# UMN_HASP_2015_Front_End_Board1.net
KiCad netlist of a schematic drawn in EAGLE
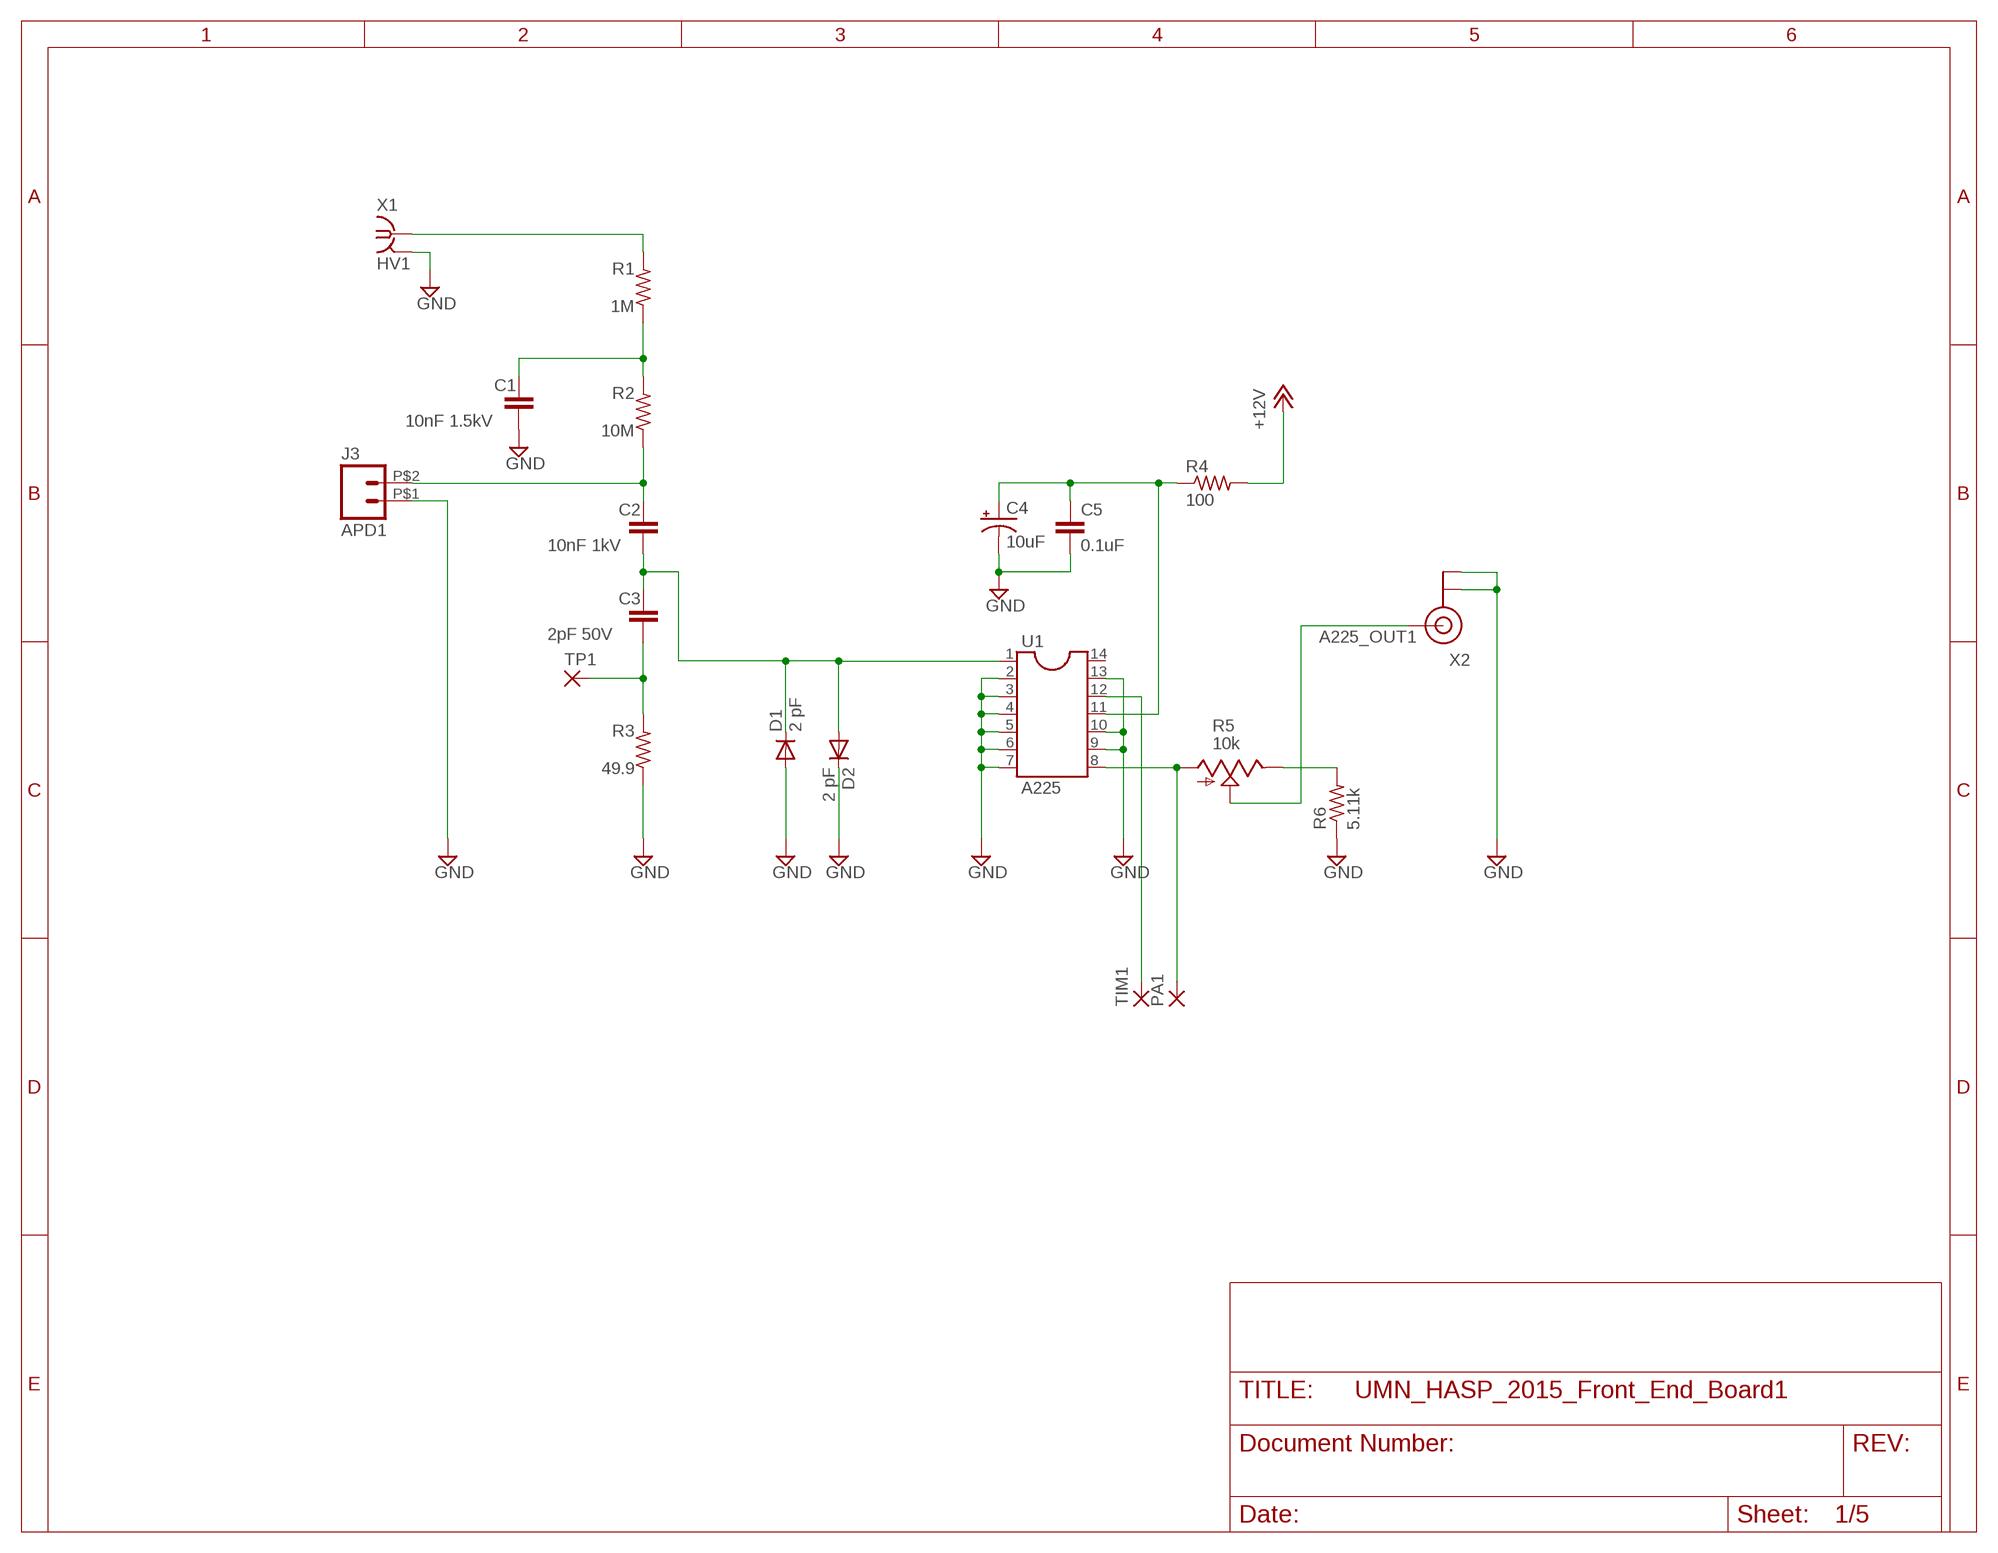
[diagram p0: schematic, sheet 1]
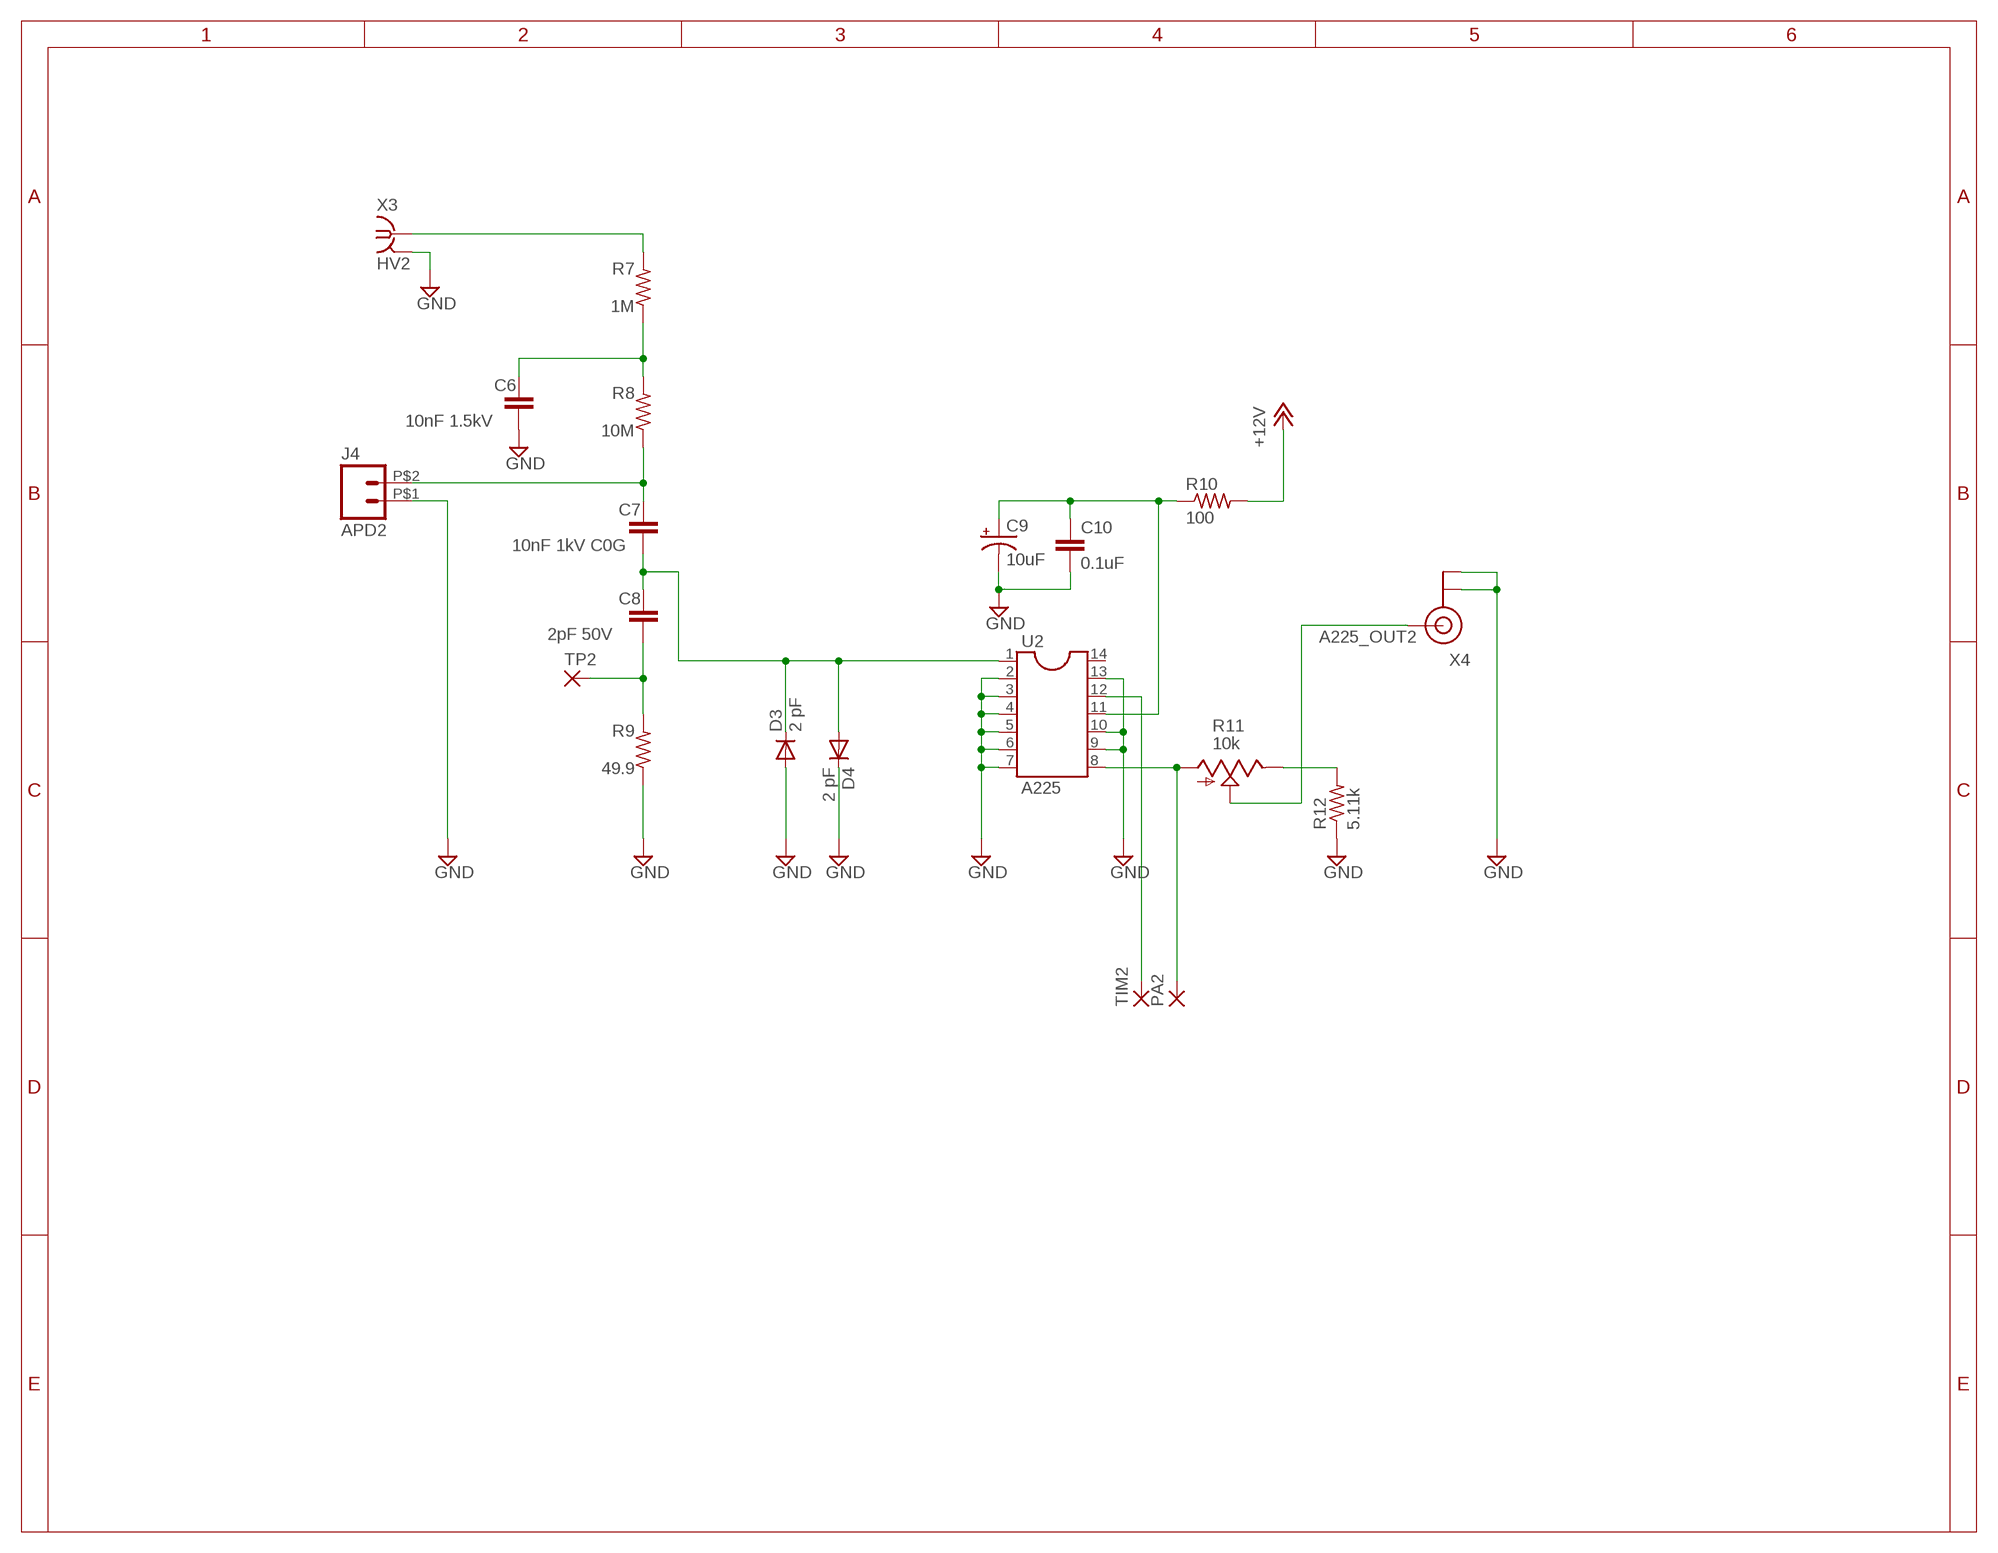
[diagram p1: schematic, sheet 2]
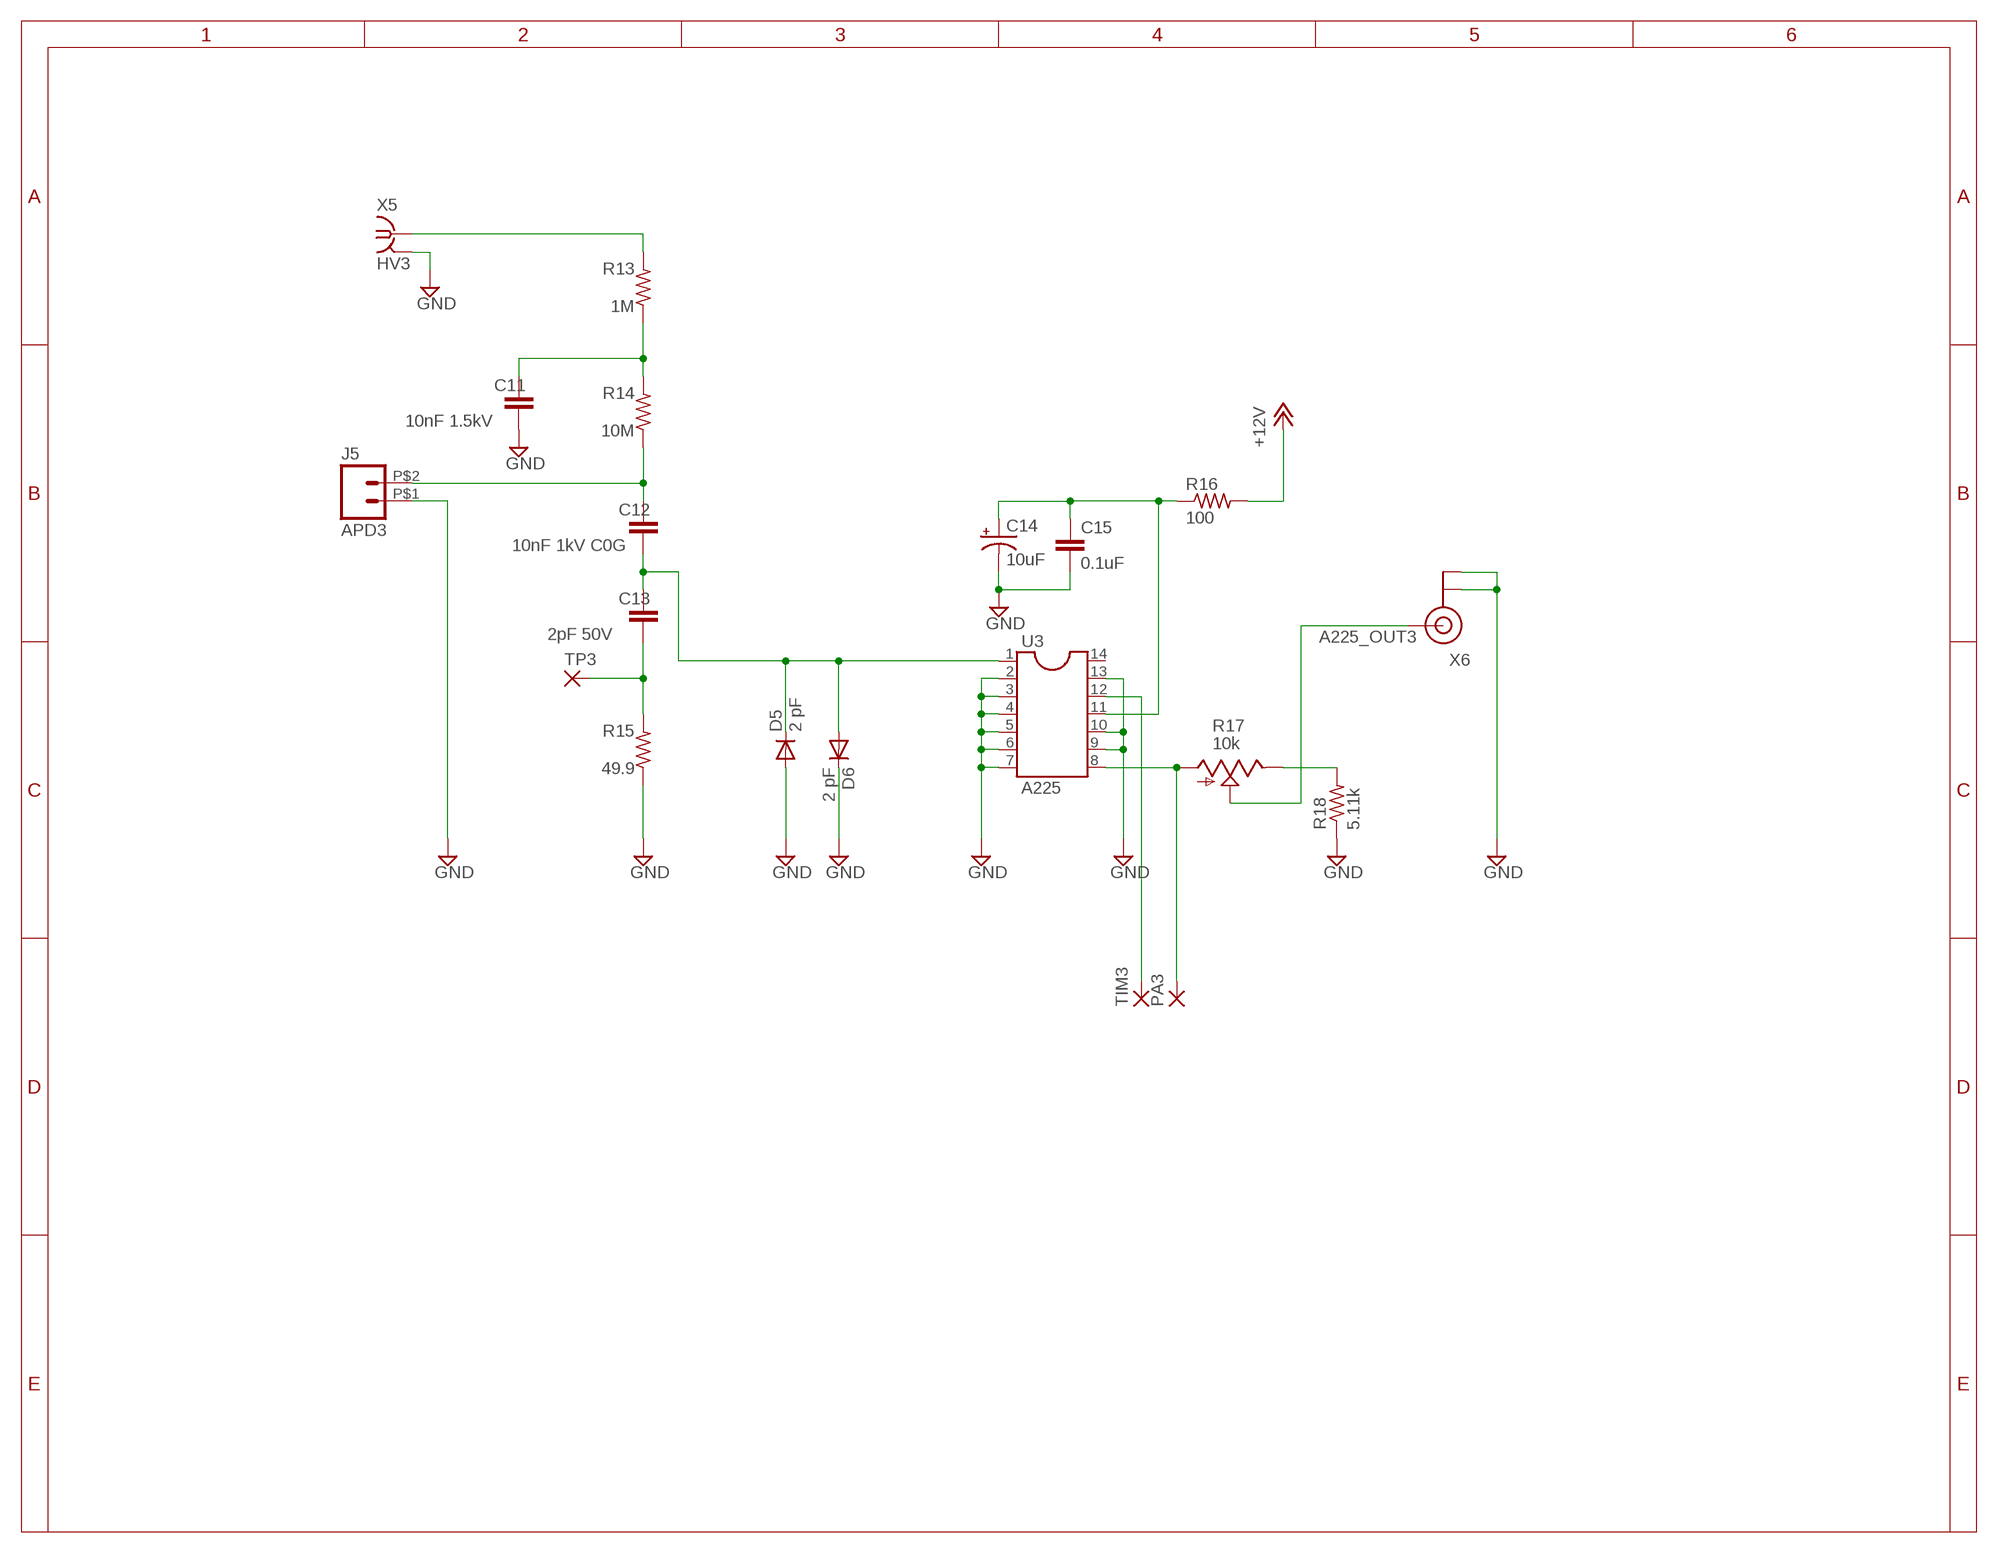
[diagram p2: schematic, sheet 3]
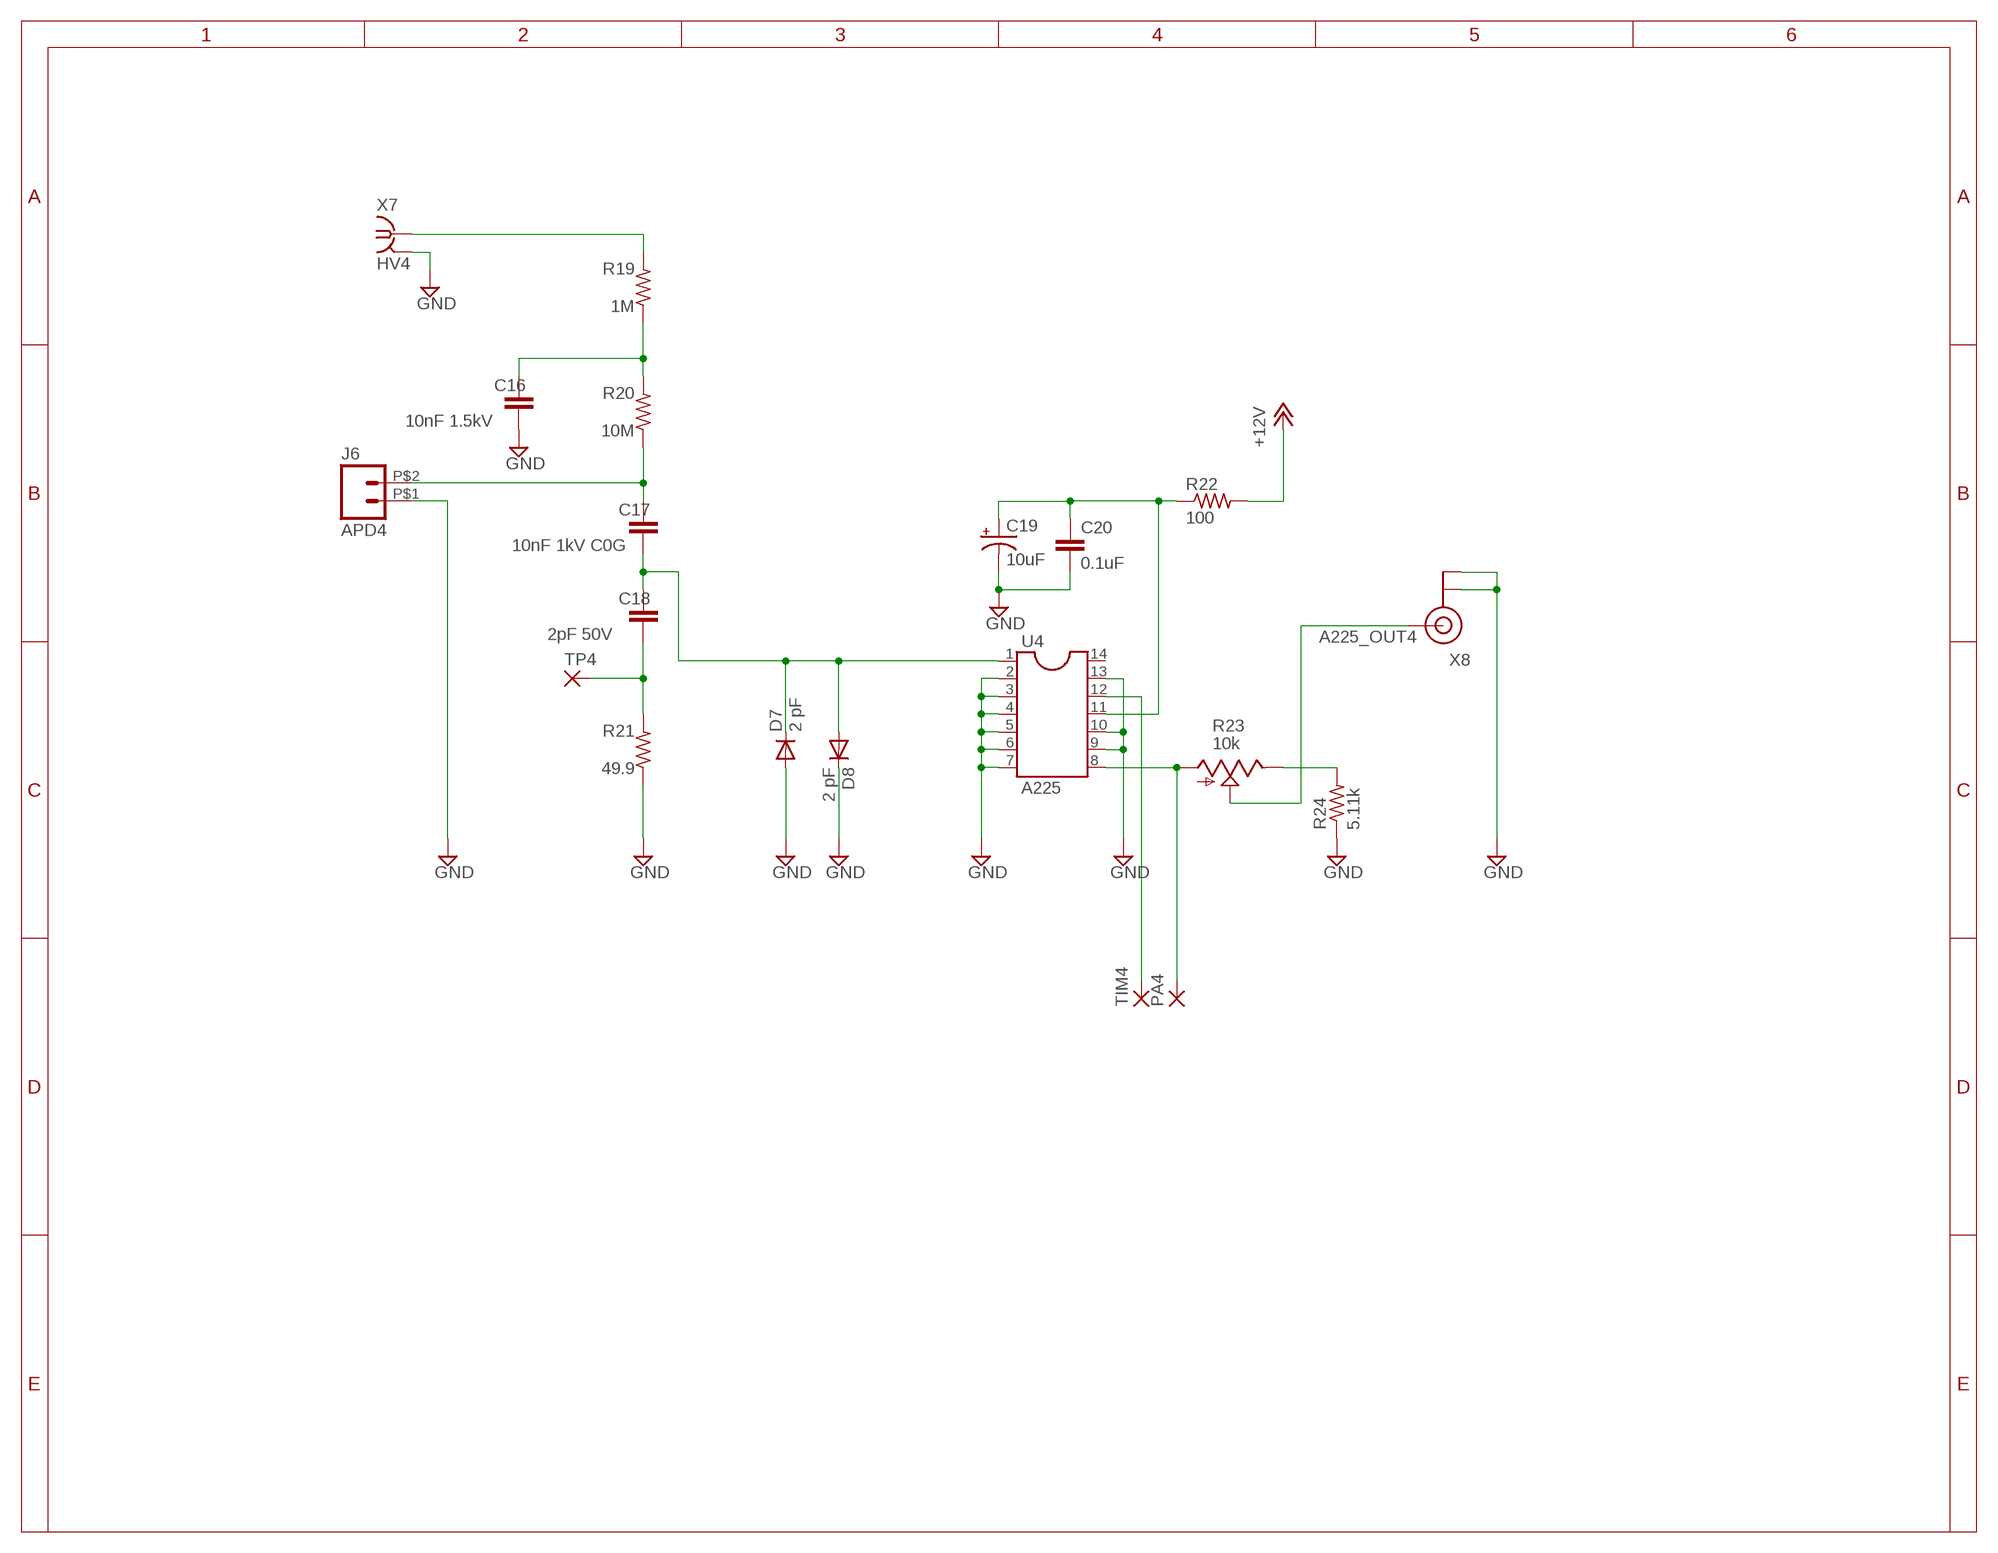
[diagram p3: schematic, sheet 4]
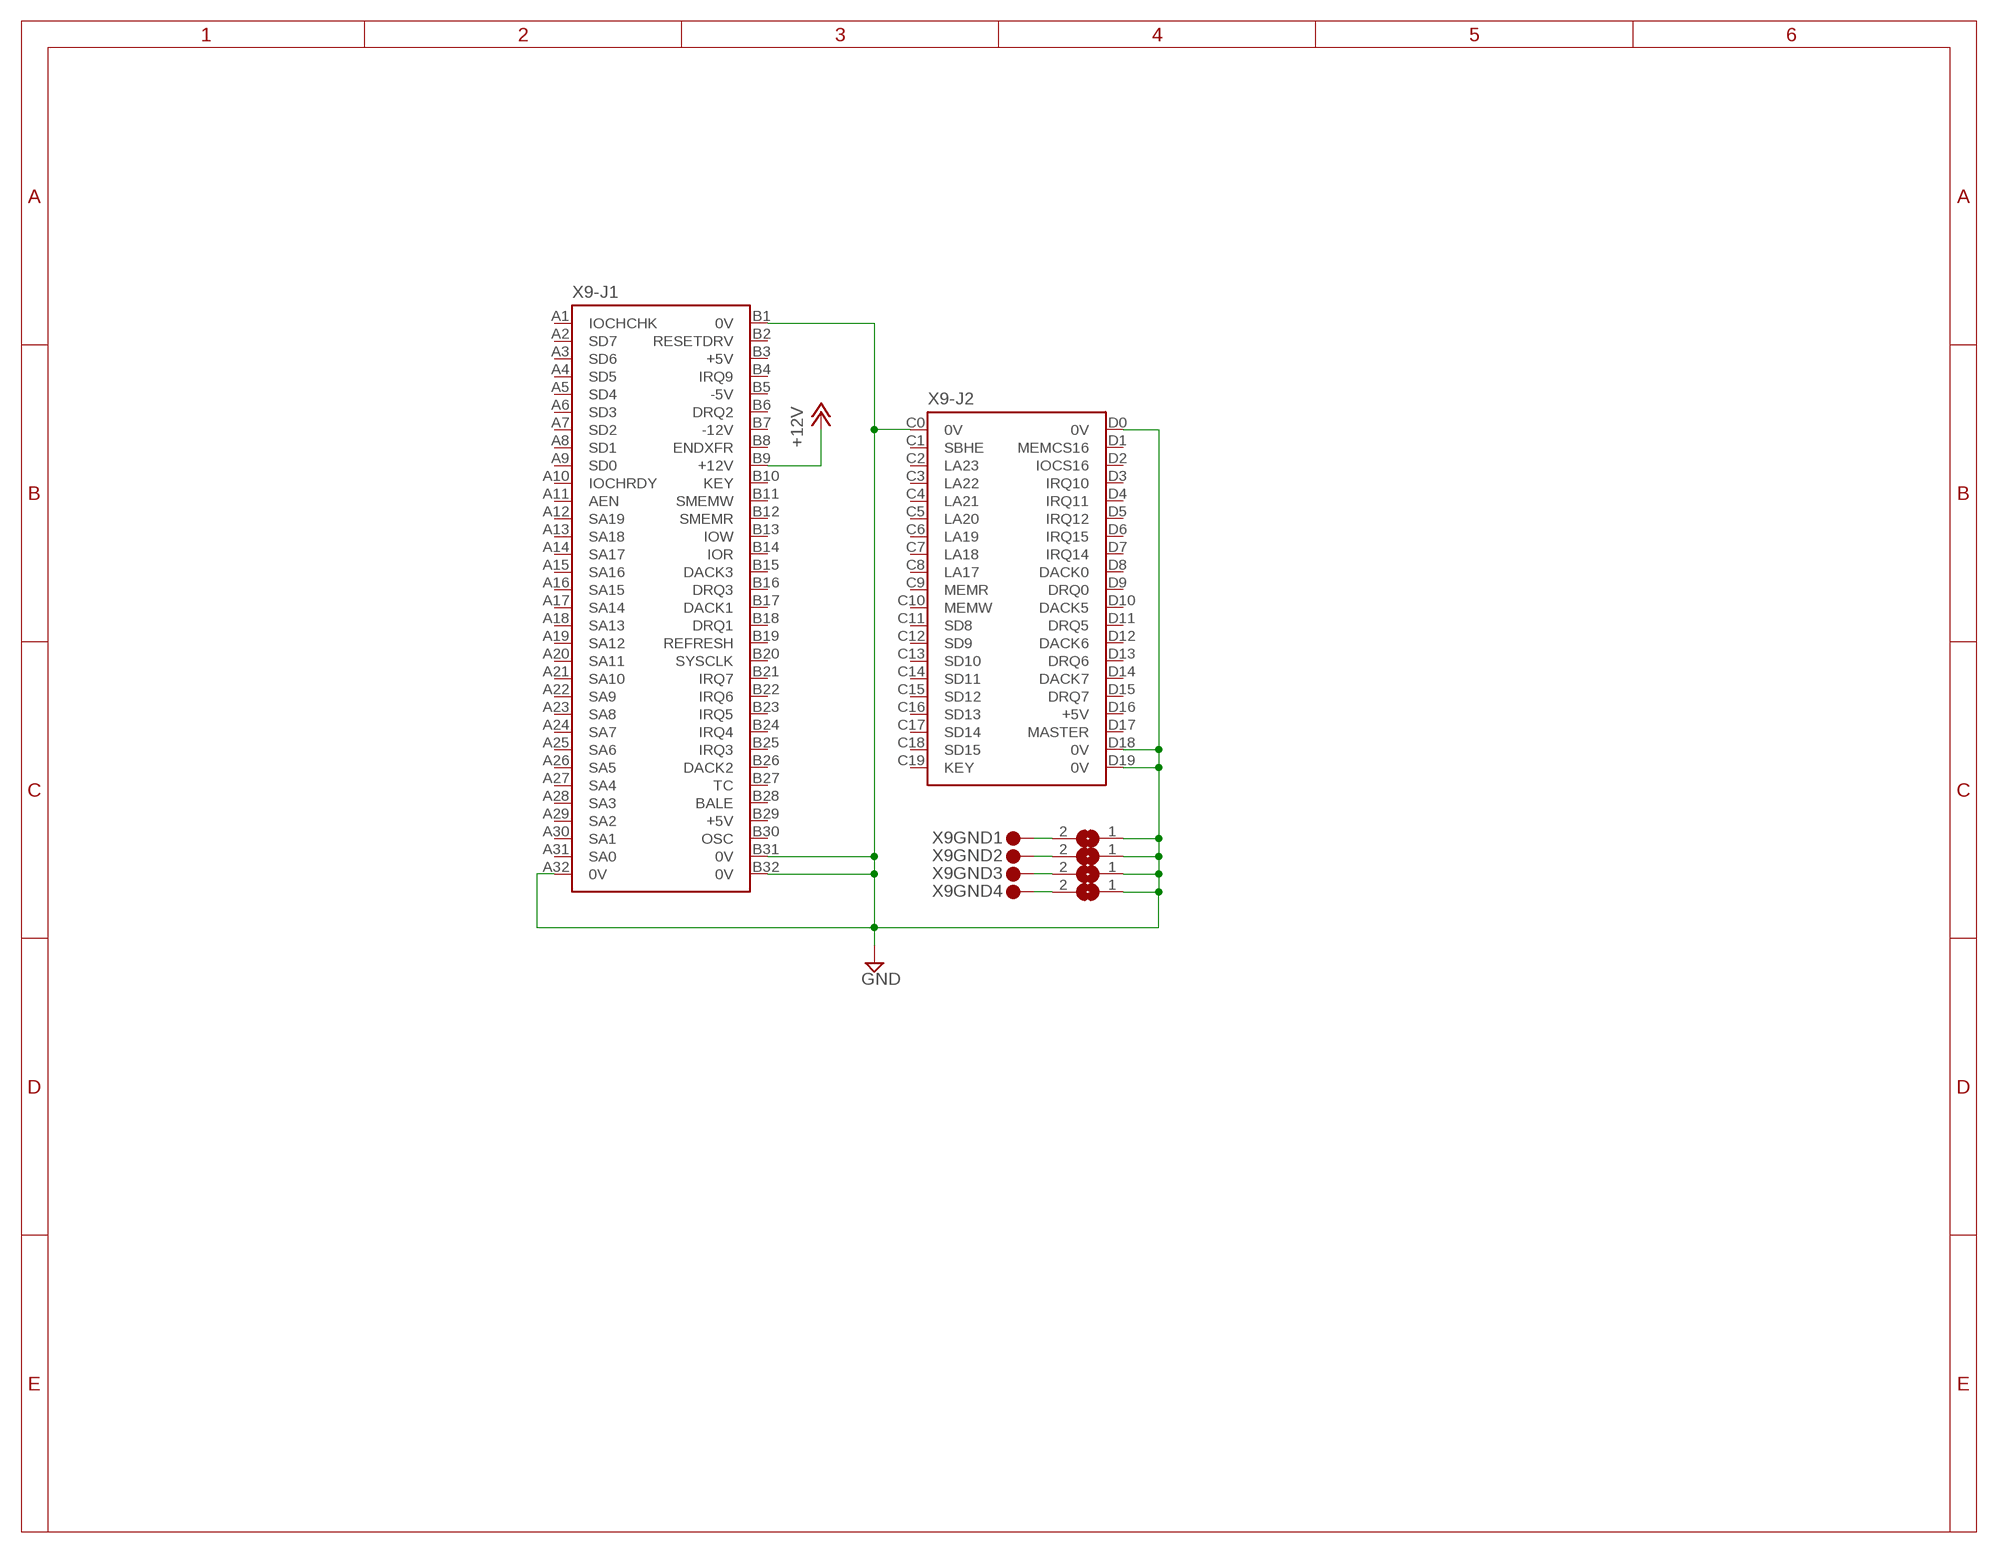
[diagram p4: schematic, sheet 5]

(export (version "E")
  (design (tool "Eeschema 10.0.6"))
  (components
    (comp (ref "SJ1") (value "SJ") (footprint "eagle-import:SJ") (libsource (lib "eagle-import") (part "SJ")))
    (comp (ref "SJ2") (value "SJ") (footprint "eagle-import:SJ") (libsource (lib "eagle-import") (part "SJ")))
    (comp (ref "SJ3") (value "SJ") (footprint "eagle-import:SJ") (libsource (lib "eagle-import") (part "SJ")))
    (comp (ref "SJ4") (value "SJ") (footprint "eagle-import:SJ") (libsource (lib "eagle-import") (part "SJ")))
    (comp (ref "X9")
      (value "PC104_STANDARD1")
      (footprint "eagle-import:PC104-STANDARD")
      (libsource (lib "eagle-import") (part "PC104_STANDARD1"))
    )
    (comp (ref "C6")
      (value "10nF 1.5kV")
      (footprint "eagle-import:C1206K")
      (libsource (lib "eagle-import") (part "C-EUC1206K"))
    )
    (comp (ref "C7")
      (value "10nF 1kV C0G")
      (footprint "eagle-import:C050-050X075")
      (libsource (lib "eagle-import") (part "C-EU050-050X075"))
    )
    (comp (ref "C8")
      (value "2pF 50V")
      (footprint "eagle-import:C0402")
      (libsource (lib "eagle-import") (part "C-EUC0402"))
    )
    (comp (ref "C9")
      (value "10uF")
      (footprint "eagle-import:C_6032-28R")
      (libsource (lib "eagle-import") (part "CPOL-USC/6032-28R"))
    )
    (comp (ref "C10")
      (value "0.1uF")
      (footprint "eagle-import:C0603K")
      (libsource (lib "eagle-import") (part "C-EUC0603K"))
    )
    (comp (ref "D3")
      (value "2 pF")
      (footprint "eagle-import:SOD323-R")
      (libsource (lib "eagle-import") (part "DIODE-SOD323-R"))
    )
    (comp (ref "D4")
      (value "2 pF")
      (footprint "eagle-import:SOD323-R")
      (libsource (lib "eagle-import") (part "DIODE-SOD323-R"))
    )
    (comp (ref "J4")
      (value "M02PTH2")
      (footprint "eagle-import:1X02_BIG")
      (libsource (lib "eagle-import") (part "M02PTH2"))
    )
    (comp (ref "PA2")
      (value "WIREPADSMD1,27-254")
      (footprint "eagle-import:SMD1,27-2,54")
      (libsource (lib "eagle-import") (part "WIREPADSMD1,27-254"))
    )
    (comp (ref "R7")
      (value "1M")
      (footprint "eagle-import:R1206")
      (libsource (lib "eagle-import") (part "R-US_R1206"))
    )
    (comp (ref "R8")
      (value "10M")
      (footprint "eagle-import:R1206")
      (libsource (lib "eagle-import") (part "R-US_R1206"))
    )
    (comp (ref "R9")
      (value "49.9")
      (footprint "eagle-import:R0603")
      (libsource (lib "eagle-import") (part "R-US_R0603"))
    )
    (comp (ref "R10")
      (value "100")
      (footprint "eagle-import:R0603")
      (libsource (lib "eagle-import") (part "R-US_R0603"))
    )
    (comp (ref "R11")
      (value "10k")
      (footprint "eagle-import:3223J")
      (libsource (lib "eagle-import") (part "TRIM_US-3223J"))
    )
    (comp (ref "R12")
      (value "5.11k")
      (footprint "eagle-import:R0603")
      (libsource (lib "eagle-import") (part "R-US_R0603"))
    )
    (comp (ref "TIM2")
      (value "WIREPADSMD1,27-254")
      (footprint "eagle-import:SMD1,27-2,54")
      (libsource (lib "eagle-import") (part "WIREPADSMD1,27-254"))
    )
    (comp (ref "TP2")
      (value "WIREPADSMD1,27-254")
      (footprint "eagle-import:SMD1,27-2,54")
      (libsource (lib "eagle-import") (part "WIREPADSMD1,27-254"))
    )
    (comp (ref "U2")
      (value "A225")
      (footprint "eagle-import:SOCKET-14")
      (libsource (lib "eagle-import") (part "DIL14S"))
    )
    (comp (ref "X3")
      (value "HV2")
      (footprint "eagle-import:BU-SMA-V")
      (libsource (lib "eagle-import") (part "BU-SMA-V"))
    )
    (comp (ref "X4")
      (value "U.FL")
      (footprint "eagle-import:U.FL")
      (libsource (lib "eagle-import") (part "U.FL"))
    )
    (comp (ref "C16")
      (value "10nF 1.5kV")
      (footprint "eagle-import:C1206K")
      (libsource (lib "eagle-import") (part "C-EUC1206K"))
    )
    (comp (ref "C17")
      (value "10nF 1kV C0G")
      (footprint "eagle-import:C050-050X075")
      (libsource (lib "eagle-import") (part "C-EU050-050X075"))
    )
    (comp (ref "C18")
      (value "2pF 50V")
      (footprint "eagle-import:C0402")
      (libsource (lib "eagle-import") (part "C-EUC0402"))
    )
    (comp (ref "C19")
      (value "10uF")
      (footprint "eagle-import:C_6032-28R")
      (libsource (lib "eagle-import") (part "CPOL-USC/6032-28R"))
    )
    (comp (ref "C20")
      (value "0.1uF")
      (footprint "eagle-import:C0603K")
      (libsource (lib "eagle-import") (part "C-EUC0603K"))
    )
    (comp (ref "D7")
      (value "2 pF")
      (footprint "eagle-import:SOD323-R")
      (libsource (lib "eagle-import") (part "DIODE-SOD323-R"))
    )
    (comp (ref "D8")
      (value "2 pF")
      (footprint "eagle-import:SOD323-R")
      (libsource (lib "eagle-import") (part "DIODE-SOD323-R"))
    )
    (comp (ref "J6")
      (value "M02PTH2")
      (footprint "eagle-import:1X02_BIG")
      (libsource (lib "eagle-import") (part "M02PTH2"))
    )
    (comp (ref "PA4")
      (value "WIREPADSMD1,27-254")
      (footprint "eagle-import:SMD1,27-2,54")
      (libsource (lib "eagle-import") (part "WIREPADSMD1,27-254"))
    )
    (comp (ref "R19")
      (value "1M")
      (footprint "eagle-import:R1206")
      (libsource (lib "eagle-import") (part "R-US_R1206"))
    )
    (comp (ref "R20")
      (value "10M")
      (footprint "eagle-import:R1206")
      (libsource (lib "eagle-import") (part "R-US_R1206"))
    )
    (comp (ref "R21")
      (value "49.9")
      (footprint "eagle-import:R0603")
      (libsource (lib "eagle-import") (part "R-US_R0603"))
    )
    (comp (ref "R22")
      (value "100")
      (footprint "eagle-import:R0603")
      (libsource (lib "eagle-import") (part "R-US_R0603"))
    )
    (comp (ref "R23")
      (value "10k")
      (footprint "eagle-import:3223J")
      (libsource (lib "eagle-import") (part "TRIM_US-3223J"))
    )
    (comp (ref "R24")
      (value "5.11k")
      (footprint "eagle-import:R0603")
      (libsource (lib "eagle-import") (part "R-US_R0603"))
    )
    (comp (ref "TIM4")
      (value "WIREPADSMD1,27-254")
      (footprint "eagle-import:SMD1,27-2,54")
      (libsource (lib "eagle-import") (part "WIREPADSMD1,27-254"))
    )
    (comp (ref "TP4")
      (value "WIREPADSMD1,27-254")
      (footprint "eagle-import:SMD1,27-2,54")
      (libsource (lib "eagle-import") (part "WIREPADSMD1,27-254"))
    )
    (comp (ref "U4")
      (value "A225")
      (footprint "eagle-import:SOCKET-14")
      (libsource (lib "eagle-import") (part "DIL14S"))
    )
    (comp (ref "X7")
      (value "HV4")
      (footprint "eagle-import:BU-SMA-V")
      (libsource (lib "eagle-import") (part "BU-SMA-V"))
    )
    (comp (ref "X8")
      (value "U.FL")
      (footprint "eagle-import:U.FL")
      (libsource (lib "eagle-import") (part "U.FL"))
    )
    (comp (ref "C1")
      (value "10nF 1.5kV")
      (footprint "eagle-import:C1206K")
      (libsource (lib "eagle-import") (part "C-EUC1206K"))
    )
    (comp (ref "C2")
      (value "10nF 1kV")
      (footprint "eagle-import:C050-050X075")
      (libsource (lib "eagle-import") (part "C-EU050-050X075"))
    )
    (comp (ref "C3")
      (value "2pF 50V")
      (footprint "eagle-import:C0402")
      (libsource (lib "eagle-import") (part "C-EUC0402"))
    )
    (comp (ref "C4")
      (value "10uF")
      (footprint "eagle-import:C_6032-28R")
      (libsource (lib "eagle-import") (part "CPOL-USC/6032-28R"))
    )
    (comp (ref "C5")
      (value "0.1uF")
      (footprint "eagle-import:C0603K")
      (libsource (lib "eagle-import") (part "C-EUC0603K"))
    )
    (comp (ref "D1")
      (value "2 pF")
      (footprint "eagle-import:SOD323-R")
      (libsource (lib "eagle-import") (part "DIODE-SOD323-R"))
    )
    (comp (ref "D2")
      (value "2 pF")
      (footprint "eagle-import:SOD323-R")
      (libsource (lib "eagle-import") (part "DIODE-SOD323-R"))
    )
    (comp (ref "J3")
      (value "M02PTH2")
      (footprint "eagle-import:1X02_BIG")
      (libsource (lib "eagle-import") (part "M02PTH2"))
    )
    (comp (ref "PA1")
      (value "WIREPADSMD1,27-254")
      (footprint "eagle-import:SMD1,27-2,54")
      (libsource (lib "eagle-import") (part "WIREPADSMD1,27-254"))
    )
    (comp (ref "R1")
      (value "1M")
      (footprint "eagle-import:R1206")
      (libsource (lib "eagle-import") (part "R-US_R1206"))
    )
    (comp (ref "R2")
      (value "10M")
      (footprint "eagle-import:R1206")
      (libsource (lib "eagle-import") (part "R-US_R1206"))
    )
    (comp (ref "R3")
      (value "49.9")
      (footprint "eagle-import:R0603")
      (libsource (lib "eagle-import") (part "R-US_R0603"))
    )
    (comp (ref "R4")
      (value "100")
      (footprint "eagle-import:R0603")
      (libsource (lib "eagle-import") (part "R-US_R0603"))
    )
    (comp (ref "R5")
      (value "10k")
      (footprint "eagle-import:3223J")
      (libsource (lib "eagle-import") (part "TRIM_US-3223J"))
    )
    (comp (ref "R6")
      (value "5.11k")
      (footprint "eagle-import:R0603")
      (libsource (lib "eagle-import") (part "R-US_R0603"))
    )
    (comp (ref "TIM1")
      (value "WIREPADSMD1,27-254")
      (footprint "eagle-import:SMD1,27-2,54")
      (libsource (lib "eagle-import") (part "WIREPADSMD1,27-254"))
    )
    (comp (ref "TP1")
      (value "WIREPADSMD1,27-254")
      (footprint "eagle-import:SMD1,27-2,54")
      (libsource (lib "eagle-import") (part "WIREPADSMD1,27-254"))
    )
    (comp (ref "U1")
      (value "A225")
      (footprint "eagle-import:SOCKET-14")
      (libsource (lib "eagle-import") (part "DIL14S"))
    )
    (comp (ref "X1")
      (value "HV1")
      (footprint "eagle-import:BU-SMA-V")
      (libsource (lib "eagle-import") (part "BU-SMA-V"))
    )
    (comp (ref "X2")
      (value "U.FL")
      (footprint "eagle-import:U.FL")
      (libsource (lib "eagle-import") (part "U.FL"))
    )
    (comp (ref "C11")
      (value "10nF 1.5kV")
      (footprint "eagle-import:C1206K")
      (libsource (lib "eagle-import") (part "C-EUC1206K"))
    )
    (comp (ref "C12")
      (value "10nF 1kV C0G")
      (footprint "eagle-import:C050-050X075")
      (libsource (lib "eagle-import") (part "C-EU050-050X075"))
    )
    (comp (ref "C13")
      (value "2pF 50V")
      (footprint "eagle-import:C0402")
      (libsource (lib "eagle-import") (part "C-EUC0402"))
    )
    (comp (ref "C14")
      (value "10uF")
      (footprint "eagle-import:C_6032-28R")
      (libsource (lib "eagle-import") (part "CPOL-USC/6032-28R"))
    )
    (comp (ref "C15")
      (value "0.1uF")
      (footprint "eagle-import:C0603K")
      (libsource (lib "eagle-import") (part "C-EUC0603K"))
    )
    (comp (ref "D5")
      (value "2 pF")
      (footprint "eagle-import:SOD323-R")
      (libsource (lib "eagle-import") (part "DIODE-SOD323-R"))
    )
    (comp (ref "D6")
      (value "2 pF")
      (footprint "eagle-import:SOD323-R")
      (libsource (lib "eagle-import") (part "DIODE-SOD323-R"))
    )
    (comp (ref "J5")
      (value "M02PTH2")
      (footprint "eagle-import:1X02_BIG")
      (libsource (lib "eagle-import") (part "M02PTH2"))
    )
    (comp (ref "PA3")
      (value "WIREPADSMD1,27-254")
      (footprint "eagle-import:SMD1,27-2,54")
      (libsource (lib "eagle-import") (part "WIREPADSMD1,27-254"))
    )
    (comp (ref "R13")
      (value "1M")
      (footprint "eagle-import:R1206")
      (libsource (lib "eagle-import") (part "R-US_R1206"))
    )
    (comp (ref "R14")
      (value "10M")
      (footprint "eagle-import:R1206")
      (libsource (lib "eagle-import") (part "R-US_R1206"))
    )
    (comp (ref "R15")
      (value "49.9")
      (footprint "eagle-import:R0603")
      (libsource (lib "eagle-import") (part "R-US_R0603"))
    )
    (comp (ref "R16")
      (value "100")
      (footprint "eagle-import:R0603")
      (libsource (lib "eagle-import") (part "R-US_R0603"))
    )
    (comp (ref "R17")
      (value "10k")
      (footprint "eagle-import:3223J")
      (libsource (lib "eagle-import") (part "TRIM_US-3223J"))
    )
    (comp (ref "R18")
      (value "5.11k")
      (footprint "eagle-import:R0603")
      (libsource (lib "eagle-import") (part "R-US_R0603"))
    )
    (comp (ref "TIM3")
      (value "WIREPADSMD1,27-254")
      (footprint "eagle-import:SMD1,27-2,54")
      (libsource (lib "eagle-import") (part "WIREPADSMD1,27-254"))
    )
    (comp (ref "TP3")
      (value "WIREPADSMD1,27-254")
      (footprint "eagle-import:SMD1,27-2,54")
      (libsource (lib "eagle-import") (part "WIREPADSMD1,27-254"))
    )
    (comp (ref "U3")
      (value "A225")
      (footprint "eagle-import:SOCKET-14")
      (libsource (lib "eagle-import") (part "DIL14S"))
    )
    (comp (ref "X5")
      (value "HV3")
      (footprint "eagle-import:BU-SMA-V")
      (libsource (lib "eagle-import") (part "BU-SMA-V"))
    )
    (comp (ref "X6")
      (value "U.FL")
      (footprint "eagle-import:U.FL")
      (libsource (lib "eagle-import") (part "U.FL"))
    )
  )
  (nets
    (net (code "1") (name "+12V") (class "Default")
      (node (ref "R10") (pin "2") (pinfunction "2_2") (pintype "passive"))
      (node (ref "R16") (pin "2") (pinfunction "2_2") (pintype "passive"))
      (node (ref "R22") (pin "2") (pinfunction "2_2") (pintype "passive"))
      (node (ref "R4") (pin "2") (pinfunction "2_2") (pintype "passive"))
      (node (ref "X9") (pin "B9") (pinfunction "+12V_B9") (pintype "passive"))
    )
    (net (code "2") (name "A225_OUT1") (class "Default")
      (node (ref "R5") (pin "2") (pinfunction "S_2") (pintype "passive"))
      (node (ref "X2") (pin "P$3") (pinfunction "SIGNAL_P$3") (pintype "bidirectional"))
    )
    (net (code "3") (name "A225_OUT2") (class "Default")
      (node (ref "R11") (pin "2") (pinfunction "S_2") (pintype "passive"))
      (node (ref "X4") (pin "P$3") (pinfunction "SIGNAL_P$3") (pintype "bidirectional"))
    )
    (net (code "4") (name "A225_OUT3") (class "Default")
      (node (ref "R17") (pin "2") (pinfunction "S_2") (pintype "passive"))
      (node (ref "X6") (pin "P$3") (pinfunction "SIGNAL_P$3") (pintype "bidirectional"))
    )
    (net (code "5") (name "A225_OUT4") (class "Default")
      (node (ref "R23") (pin "2") (pinfunction "S_2") (pintype "passive"))
      (node (ref "X8") (pin "P$3") (pinfunction "SIGNAL_P$3") (pintype "bidirectional"))
    )
    (net (code "6") (name "APD1") (class "Default")
      (node (ref "C2") (pin "1") (pinfunction "1_1") (pintype "passive"))
      (node (ref "J3") (pin "P$2") (pinfunction "2_P$2") (pintype "passive"))
      (node (ref "R2") (pin "1") (pinfunction "1_1") (pintype "passive"))
    )
    (net (code "7") (name "APD2") (class "Default")
      (node (ref "C7") (pin "1") (pinfunction "1_1") (pintype "passive"))
      (node (ref "J4") (pin "P$2") (pinfunction "2_P$2") (pintype "passive"))
      (node (ref "R8") (pin "1") (pinfunction "1_1") (pintype "passive"))
    )
    (net (code "8") (name "APD3") (class "Default")
      (node (ref "C12") (pin "1") (pinfunction "1_1") (pintype "passive"))
      (node (ref "J5") (pin "P$2") (pinfunction "2_P$2") (pintype "passive"))
      (node (ref "R14") (pin "1") (pinfunction "1_1") (pintype "passive"))
    )
    (net (code "9") (name "APD4") (class "Default")
      (node (ref "C17") (pin "1") (pinfunction "1_1") (pintype "passive"))
      (node (ref "J6") (pin "P$2") (pinfunction "2_P$2") (pintype "passive"))
      (node (ref "R20") (pin "1") (pinfunction "1_1") (pintype "passive"))
    )
    (net (code "10") (name "GND") (class "Default")
      (node (ref "C1") (pin "2") (pinfunction "2_2") (pintype "passive"))
      (node (ref "C10") (pin "2") (pinfunction "2_2") (pintype "passive"))
      (node (ref "C11") (pin "2") (pinfunction "2_2") (pintype "passive"))
      (node (ref "C14") (pin "-") (pinfunction "-_-") (pintype "passive"))
      (node (ref "C15") (pin "2") (pinfunction "2_2") (pintype "passive"))
      (node (ref "C16") (pin "2") (pinfunction "2_2") (pintype "passive"))
      (node (ref "C19") (pin "-") (pinfunction "-_-") (pintype "passive"))
      (node (ref "C20") (pin "2") (pinfunction "2_2") (pintype "passive"))
      (node (ref "C4") (pin "-") (pinfunction "-_-") (pintype "passive"))
      (node (ref "C5") (pin "2") (pinfunction "2_2") (pintype "passive"))
      (node (ref "C6") (pin "2") (pinfunction "2_2") (pintype "passive"))
      (node (ref "C9") (pin "-") (pinfunction "-_-") (pintype "passive"))
      (node (ref "D1") (pin "A") (pinfunction "A_A") (pintype "passive"))
      (node (ref "D2") (pin "C") (pinfunction "C_C") (pintype "passive"))
      (node (ref "D3") (pin "A") (pinfunction "A_A") (pintype "passive"))
      (node (ref "D4") (pin "C") (pinfunction "C_C") (pintype "passive"))
      (node (ref "D5") (pin "A") (pinfunction "A_A") (pintype "passive"))
      (node (ref "D6") (pin "C") (pinfunction "C_C") (pintype "passive"))
      (node (ref "D7") (pin "A") (pinfunction "A_A") (pintype "passive"))
      (node (ref "D8") (pin "C") (pinfunction "C_C") (pintype "passive"))
      (node (ref "J3") (pin "P$1") (pinfunction "1_P$1") (pintype "passive"))
      (node (ref "J4") (pin "P$1") (pinfunction "1_P$1") (pintype "passive"))
      (node (ref "J5") (pin "P$1") (pinfunction "1_P$1") (pintype "passive"))
      (node (ref "J6") (pin "P$1") (pinfunction "1_P$1") (pintype "passive"))
      (node (ref "R12") (pin "1") (pinfunction "1_1") (pintype "passive"))
      (node (ref "R15") (pin "1") (pinfunction "1_1") (pintype "passive"))
      (node (ref "R18") (pin "1") (pinfunction "1_1") (pintype "passive"))
      (node (ref "R21") (pin "1") (pinfunction "1_1") (pintype "passive"))
      (node (ref "R24") (pin "1") (pinfunction "1_1") (pintype "passive"))
      (node (ref "R3") (pin "1") (pinfunction "1_1") (pintype "passive"))
      (node (ref "R6") (pin "1") (pinfunction "1_1") (pintype "passive"))
      (node (ref "R9") (pin "1") (pinfunction "1_1") (pintype "passive"))
      (node (ref "SJ1") (pin "1") (pinfunction "1_1") (pintype "passive"))
      (node (ref "SJ2") (pin "1") (pinfunction "1_1") (pintype "passive"))
      (node (ref "SJ3") (pin "1") (pinfunction "1_1") (pintype "passive"))
      (node (ref "SJ4") (pin "1") (pinfunction "1_1") (pintype "passive"))
      (node (ref "U1") (pin "10") (pinfunction "10_10") (pintype "passive"))
      (node (ref "U1") (pin "13") (pinfunction "13_13") (pintype "passive"))
      (node (ref "U1") (pin "2") (pinfunction "2_2") (pintype "passive"))
      (node (ref "U1") (pin "3") (pinfunction "3_3") (pintype "passive"))
      (node (ref "U1") (pin "4") (pinfunction "4_4") (pintype "passive"))
      (node (ref "U1") (pin "5") (pinfunction "5_5") (pintype "passive"))
      (node (ref "U1") (pin "6") (pinfunction "6_6") (pintype "passive"))
      (node (ref "U1") (pin "7") (pinfunction "7_7") (pintype "passive"))
      (node (ref "U1") (pin "9") (pinfunction "9_9") (pintype "passive"))
      (node (ref "U2") (pin "10") (pinfunction "10_10") (pintype "passive"))
      (node (ref "U2") (pin "13") (pinfunction "13_13") (pintype "passive"))
      (node (ref "U2") (pin "2") (pinfunction "2_2") (pintype "passive"))
      (node (ref "U2") (pin "3") (pinfunction "3_3") (pintype "passive"))
      (node (ref "U2") (pin "4") (pinfunction "4_4") (pintype "passive"))
      (node (ref "U2") (pin "5") (pinfunction "5_5") (pintype "passive"))
      (node (ref "U2") (pin "6") (pinfunction "6_6") (pintype "passive"))
      (node (ref "U2") (pin "7") (pinfunction "7_7") (pintype "passive"))
      (node (ref "U2") (pin "9") (pinfunction "9_9") (pintype "passive"))
      (node (ref "U3") (pin "10") (pinfunction "10_10") (pintype "passive"))
      (node (ref "U3") (pin "13") (pinfunction "13_13") (pintype "passive"))
      (node (ref "U3") (pin "2") (pinfunction "2_2") (pintype "passive"))
      (node (ref "U3") (pin "3") (pinfunction "3_3") (pintype "passive"))
      (node (ref "U3") (pin "4") (pinfunction "4_4") (pintype "passive"))
      (node (ref "U3") (pin "5") (pinfunction "5_5") (pintype "passive"))
      (node (ref "U3") (pin "6") (pinfunction "6_6") (pintype "passive"))
      (node (ref "U3") (pin "7") (pinfunction "7_7") (pintype "passive"))
      (node (ref "U3") (pin "9") (pinfunction "9_9") (pintype "passive"))
      (node (ref "U4") (pin "10") (pinfunction "10_10") (pintype "passive"))
      (node (ref "U4") (pin "13") (pinfunction "13_13") (pintype "passive"))
      (node (ref "U4") (pin "2") (pinfunction "2_2") (pintype "passive"))
      (node (ref "U4") (pin "3") (pinfunction "3_3") (pintype "passive"))
      (node (ref "U4") (pin "4") (pinfunction "4_4") (pintype "passive"))
      (node (ref "U4") (pin "5") (pinfunction "5_5") (pintype "passive"))
      (node (ref "U4") (pin "6") (pinfunction "6_6") (pintype "passive"))
      (node (ref "U4") (pin "7") (pinfunction "7_7") (pintype "passive"))
      (node (ref "U4") (pin "9") (pinfunction "9_9") (pintype "passive"))
      (node (ref "X1") (pin "2") (pinfunction "GND_2") (pintype "power_in"))
      (node (ref "X2") (pin "P$1") (pinfunction "GND_P$1") (pintype "bidirectional"))
      (node (ref "X2") (pin "P$2") (pinfunction "GND_P$2") (pintype "bidirectional"))
      (node (ref "X3") (pin "2") (pinfunction "GND_2") (pintype "power_in"))
      (node (ref "X4") (pin "P$1") (pinfunction "GND_P$1") (pintype "bidirectional"))
      (node (ref "X4") (pin "P$2") (pinfunction "GND_P$2") (pintype "bidirectional"))
      (node (ref "X5") (pin "2") (pinfunction "GND_2") (pintype "power_in"))
      (node (ref "X6") (pin "P$1") (pinfunction "GND_P$1") (pintype "bidirectional"))
      (node (ref "X6") (pin "P$2") (pinfunction "GND_P$2") (pintype "bidirectional"))
      (node (ref "X7") (pin "2") (pinfunction "GND_2") (pintype "power_in"))
      (node (ref "X8") (pin "P$1") (pinfunction "GND_P$1") (pintype "bidirectional"))
      (node (ref "X8") (pin "P$2") (pinfunction "GND_P$2") (pintype "bidirectional"))
      (node (ref "X9") (pin "A32") (pinfunction "0V_A32") (pintype "passive"))
      (node (ref "X9") (pin "B1") (pinfunction "0V_B1") (pintype "passive"))
      (node (ref "X9") (pin "B31") (pinfunction "0V_B31") (pintype "passive"))
      (node (ref "X9") (pin "B32") (pinfunction "0V_B32") (pintype "passive"))
      (node (ref "X9") (pin "C0") (pinfunction "0V_C0") (pintype "passive"))
      (node (ref "X9") (pin "D0") (pinfunction "0V_D0") (pintype "passive"))
      (node (ref "X9") (pin "D18") (pinfunction "0V_D18") (pintype "passive"))
      (node (ref "X9") (pin "D19") (pinfunction "0V_D19") (pintype "passive"))
    )
    (net (code "11") (name "Net-(C1-Pad1)") (class "Default")
      (node (ref "C1") (pin "1") (pinfunction "1_1") (pintype "passive"))
      (node (ref "R1") (pin "1") (pinfunction "1_1") (pintype "passive"))
      (node (ref "R2") (pin "2") (pinfunction "2_2") (pintype "passive"))
    )
    (net (code "12") (name "Net-(C2-Pad2)") (class "Default")
      (node (ref "C2") (pin "2") (pinfunction "2_2") (pintype "passive"))
      (node (ref "C3") (pin "1") (pinfunction "1_1") (pintype "passive"))
      (node (ref "D1") (pin "C") (pinfunction "C_C") (pintype "passive"))
      (node (ref "D2") (pin "A") (pinfunction "A_A") (pintype "passive"))
      (node (ref "U1") (pin "1") (pinfunction "1_1") (pintype "passive"))
    )
    (net (code "13") (name "Net-(C4-Pad+)") (class "Default")
      (node (ref "C4") (pin "+") (pinfunction "+_+") (pintype "passive"))
      (node (ref "C5") (pin "1") (pinfunction "1_1") (pintype "passive"))
      (node (ref "R4") (pin "1") (pinfunction "1_1") (pintype "passive"))
      (node (ref "U1") (pin "11") (pinfunction "11_11") (pintype "passive"))
    )
    (net (code "14") (name "Net-(C6-Pad1)") (class "Default")
      (node (ref "C6") (pin "1") (pinfunction "1_1") (pintype "passive"))
      (node (ref "R7") (pin "1") (pinfunction "1_1") (pintype "passive"))
      (node (ref "R8") (pin "2") (pinfunction "2_2") (pintype "passive"))
    )
    (net (code "15") (name "Net-(C7-Pad2)") (class "Default")
      (node (ref "C7") (pin "2") (pinfunction "2_2") (pintype "passive"))
      (node (ref "C8") (pin "1") (pinfunction "1_1") (pintype "passive"))
      (node (ref "D3") (pin "C") (pinfunction "C_C") (pintype "passive"))
      (node (ref "D4") (pin "A") (pinfunction "A_A") (pintype "passive"))
      (node (ref "U2") (pin "1") (pinfunction "1_1") (pintype "passive"))
    )
    (net (code "16") (name "Net-(C10-Pad1)") (class "Default")
      (node (ref "C10") (pin "1") (pinfunction "1_1") (pintype "passive"))
      (node (ref "C9") (pin "+") (pinfunction "+_+") (pintype "passive"))
      (node (ref "R10") (pin "1") (pinfunction "1_1") (pintype "passive"))
      (node (ref "U2") (pin "11") (pinfunction "11_11") (pintype "passive"))
    )
    (net (code "17") (name "Net-(C11-Pad1)") (class "Default")
      (node (ref "C11") (pin "1") (pinfunction "1_1") (pintype "passive"))
      (node (ref "R13") (pin "1") (pinfunction "1_1") (pintype "passive"))
      (node (ref "R14") (pin "2") (pinfunction "2_2") (pintype "passive"))
    )
    (net (code "18") (name "Net-(C12-Pad2)") (class "Default")
      (node (ref "C12") (pin "2") (pinfunction "2_2") (pintype "passive"))
      (node (ref "C13") (pin "1") (pinfunction "1_1") (pintype "passive"))
      (node (ref "D5") (pin "C") (pinfunction "C_C") (pintype "passive"))
      (node (ref "D6") (pin "A") (pinfunction "A_A") (pintype "passive"))
      (node (ref "U3") (pin "1") (pinfunction "1_1") (pintype "passive"))
    )
    (net (code "19") (name "Net-(C14-Pad+)") (class "Default")
      (node (ref "C14") (pin "+") (pinfunction "+_+") (pintype "passive"))
      (node (ref "C15") (pin "1") (pinfunction "1_1") (pintype "passive"))
      (node (ref "R16") (pin "1") (pinfunction "1_1") (pintype "passive"))
      (node (ref "U3") (pin "11") (pinfunction "11_11") (pintype "passive"))
    )
    (net (code "20") (name "Net-(C16-Pad1)") (class "Default")
      (node (ref "C16") (pin "1") (pinfunction "1_1") (pintype "passive"))
      (node (ref "R19") (pin "1") (pinfunction "1_1") (pintype "passive"))
      (node (ref "R20") (pin "2") (pinfunction "2_2") (pintype "passive"))
    )
    (net (code "21") (name "Net-(C17-Pad2)") (class "Default")
      (node (ref "C17") (pin "2") (pinfunction "2_2") (pintype "passive"))
      (node (ref "C18") (pin "1") (pinfunction "1_1") (pintype "passive"))
      (node (ref "D7") (pin "C") (pinfunction "C_C") (pintype "passive"))
      (node (ref "D8") (pin "A") (pinfunction "A_A") (pintype "passive"))
      (node (ref "U4") (pin "1") (pinfunction "1_1") (pintype "passive"))
    )
    (net (code "22") (name "Net-(C19-Pad+)") (class "Default")
      (node (ref "C19") (pin "+") (pinfunction "+_+") (pintype "passive"))
      (node (ref "C20") (pin "1") (pinfunction "1_1") (pintype "passive"))
      (node (ref "R22") (pin "1") (pinfunction "1_1") (pintype "passive"))
      (node (ref "U4") (pin "11") (pinfunction "11_11") (pintype "passive"))
    )
    (net (code "23") (name "Net-(PA1-P)") (class "Default")
      (node (ref "PA1") (pin "1") (pinfunction "P_1") (pintype "passive"))
      (node (ref "R5") (pin "1") (pinfunction "A_1") (pintype "passive"))
      (node (ref "U1") (pin "8") (pinfunction "8_8") (pintype "passive"))
    )
    (net (code "24") (name "Net-(PA2-P)") (class "Default")
      (node (ref "PA2") (pin "1") (pinfunction "P_1") (pintype "passive"))
      (node (ref "R11") (pin "1") (pinfunction "A_1") (pintype "passive"))
      (node (ref "U2") (pin "8") (pinfunction "8_8") (pintype "passive"))
    )
    (net (code "25") (name "Net-(PA3-P)") (class "Default")
      (node (ref "PA3") (pin "1") (pinfunction "P_1") (pintype "passive"))
      (node (ref "R17") (pin "1") (pinfunction "A_1") (pintype "passive"))
      (node (ref "U3") (pin "8") (pinfunction "8_8") (pintype "passive"))
    )
    (net (code "26") (name "Net-(PA4-P)") (class "Default")
      (node (ref "PA4") (pin "1") (pinfunction "P_1") (pintype "passive"))
      (node (ref "R23") (pin "1") (pinfunction "A_1") (pintype "passive"))
      (node (ref "U4") (pin "8") (pinfunction "8_8") (pintype "passive"))
    )
    (net (code "27") (name "Net-(R1-Pad2)") (class "Default")
      (node (ref "R1") (pin "2") (pinfunction "2_2") (pintype "passive"))
      (node (ref "X1") (pin "1") (pinfunction "1_1") (pintype "passive"))
    )
    (net (code "28") (name "Net-(R5-E)") (class "Default")
      (node (ref "R5") (pin "3") (pinfunction "E_3") (pintype "passive"))
      (node (ref "R6") (pin "2") (pinfunction "2_2") (pintype "passive"))
    )
    (net (code "29") (name "Net-(R7-Pad2)") (class "Default")
      (node (ref "R7") (pin "2") (pinfunction "2_2") (pintype "passive"))
      (node (ref "X3") (pin "1") (pinfunction "1_1") (pintype "passive"))
    )
    (net (code "30") (name "Net-(R11-E)") (class "Default")
      (node (ref "R11") (pin "3") (pinfunction "E_3") (pintype "passive"))
      (node (ref "R12") (pin "2") (pinfunction "2_2") (pintype "passive"))
    )
    (net (code "31") (name "Net-(R13-Pad2)") (class "Default")
      (node (ref "R13") (pin "2") (pinfunction "2_2") (pintype "passive"))
      (node (ref "X5") (pin "1") (pinfunction "1_1") (pintype "passive"))
    )
    (net (code "32") (name "Net-(R17-E)") (class "Default")
      (node (ref "R17") (pin "3") (pinfunction "E_3") (pintype "passive"))
      (node (ref "R18") (pin "2") (pinfunction "2_2") (pintype "passive"))
    )
    (net (code "33") (name "Net-(R19-Pad2)") (class "Default")
      (node (ref "R19") (pin "2") (pinfunction "2_2") (pintype "passive"))
      (node (ref "X7") (pin "1") (pinfunction "1_1") (pintype "passive"))
    )
    (net (code "34") (name "Net-(R23-E)") (class "Default")
      (node (ref "R23") (pin "3") (pinfunction "E_3") (pintype "passive"))
      (node (ref "R24") (pin "2") (pinfunction "2_2") (pintype "passive"))
    )
    (net (code "35") (name "Net-(TIM1-P)") (class "Default")
      (node (ref "TIM1") (pin "1") (pinfunction "P_1") (pintype "passive"))
      (node (ref "U1") (pin "12") (pinfunction "12_12") (pintype "passive"))
    )
    (net (code "36") (name "Net-(TIM2-P)") (class "Default")
      (node (ref "TIM2") (pin "1") (pinfunction "P_1") (pintype "passive"))
      (node (ref "U2") (pin "12") (pinfunction "12_12") (pintype "passive"))
    )
    (net (code "37") (name "Net-(TIM3-P)") (class "Default")
      (node (ref "TIM3") (pin "1") (pinfunction "P_1") (pintype "passive"))
      (node (ref "U3") (pin "12") (pinfunction "12_12") (pintype "passive"))
    )
    (net (code "38") (name "Net-(TIM4-P)") (class "Default")
      (node (ref "TIM4") (pin "1") (pinfunction "P_1") (pintype "passive"))
      (node (ref "U4") (pin "12") (pinfunction "12_12") (pintype "passive"))
    )
    (net (code "39") (name "Net-(TP1-P)") (class "Default")
      (node (ref "C3") (pin "2") (pinfunction "2_2") (pintype "passive"))
      (node (ref "R3") (pin "2") (pinfunction "2_2") (pintype "passive"))
      (node (ref "TP1") (pin "1") (pinfunction "P_1") (pintype "passive"))
    )
    (net (code "40") (name "Net-(TP2-P)") (class "Default")
      (node (ref "C8") (pin "2") (pinfunction "2_2") (pintype "passive"))
      (node (ref "R9") (pin "2") (pinfunction "2_2") (pintype "passive"))
      (node (ref "TP2") (pin "1") (pinfunction "P_1") (pintype "passive"))
    )
    (net (code "41") (name "Net-(TP3-P)") (class "Default")
      (node (ref "C13") (pin "2") (pinfunction "2_2") (pintype "passive"))
      (node (ref "R15") (pin "2") (pinfunction "2_2") (pintype "passive"))
      (node (ref "TP3") (pin "1") (pinfunction "P_1") (pintype "passive"))
    )
    (net (code "42") (name "Net-(TP4-P)") (class "Default")
      (node (ref "C18") (pin "2") (pinfunction "2_2") (pintype "passive"))
      (node (ref "R21") (pin "2") (pinfunction "2_2") (pintype "passive"))
      (node (ref "TP4") (pin "1") (pinfunction "P_1") (pintype "passive"))
    )
    (net (code "43") (name "Net-(X9C-1)") (class "Default")
      (node (ref "SJ1") (pin "2") (pinfunction "2_2") (pintype "passive"))
      (node (ref "X9") (pin "GND@1") (pinfunction "1_GND@1") (pintype "passive"))
    )
    (net (code "44") (name "Net-(X9D-1)") (class "Default")
      (node (ref "SJ2") (pin "2") (pinfunction "2_2") (pintype "passive"))
      (node (ref "X9") (pin "GND@2") (pinfunction "1_GND@2") (pintype "passive"))
    )
    (net (code "45") (name "Net-(X9E-1)") (class "Default")
      (node (ref "SJ3") (pin "2") (pinfunction "2_2") (pintype "passive"))
      (node (ref "X9") (pin "GND@3") (pinfunction "1_GND@3") (pintype "passive"))
    )
    (net (code "46") (name "Net-(X9F-1)") (class "Default")
      (node (ref "SJ4") (pin "2") (pinfunction "2_2") (pintype "passive"))
      (node (ref "X9") (pin "GND@4") (pinfunction "1_GND@4") (pintype "passive"))
    )
    (net (code "47") (name "unconnected-(U1-Pad14)") (class "Default")
      (node (ref "U1") (pin "14") (pinfunction "14_14") (pintype "passive"))
    )
    (net (code "48") (name "unconnected-(U2-Pad14)") (class "Default")
      (node (ref "U2") (pin "14") (pinfunction "14_14") (pintype "passive"))
    )
    (net (code "49") (name "unconnected-(U3-Pad14)") (class "Default")
      (node (ref "U3") (pin "14") (pinfunction "14_14") (pintype "passive"))
    )
    (net (code "50") (name "unconnected-(U4-Pad14)") (class "Default")
      (node (ref "U4") (pin "14") (pinfunction "14_14") (pintype "passive"))
    )
    (net (code "51") (name "unconnected-(X9A-+5V-PadB3)") (class "Default")
      (node (ref "X9") (pin "B3") (pinfunction "+5V_B3") (pintype "passive"))
    )
    (net (code "52") (name "unconnected-(X9A-+5V-PadB29)") (class "Default")
      (node (ref "X9") (pin "B29") (pinfunction "+5V_B29") (pintype "passive"))
    )
    (net (code "53") (name "unconnected-(X9A--5V-PadB5)") (class "Default")
      (node (ref "X9") (pin "B5") (pinfunction "-5V_B5") (pintype "passive"))
    )
    (net (code "54") (name "unconnected-(X9A--12V-PadB7)") (class "Default")
      (node (ref "X9") (pin "B7") (pinfunction "-12V_B7") (pintype "passive"))
    )
    (net (code "55") (name "unconnected-(X9A-AEN-PadA11)") (class "Default")
      (node (ref "X9") (pin "A11") (pinfunction "AEN_A11") (pintype "passive"))
    )
    (net (code "56") (name "unconnected-(X9A-BALE-PadB28)") (class "Default")
      (node (ref "X9") (pin "B28") (pinfunction "BALE_B28") (pintype "passive"))
    )
    (net (code "57") (name "unconnected-(X9A-DACK1-PadB17)") (class "Default")
      (node (ref "X9") (pin "B17") (pinfunction "DACK1_B17") (pintype "passive"))
    )
    (net (code "58") (name "unconnected-(X9A-DACK2-PadB26)") (class "Default")
      (node (ref "X9") (pin "B26") (pinfunction "DACK2_B26") (pintype "passive"))
    )
    (net (code "59") (name "unconnected-(X9A-DACK3-PadB15)") (class "Default")
      (node (ref "X9") (pin "B15") (pinfunction "DACK3_B15") (pintype "passive"))
    )
    (net (code "60") (name "unconnected-(X9A-DRQ1-PadB18)") (class "Default")
      (node (ref "X9") (pin "B18") (pinfunction "DRQ1_B18") (pintype "passive"))
    )
    (net (code "61") (name "unconnected-(X9A-DRQ2-PadB6)") (class "Default")
      (node (ref "X9") (pin "B6") (pinfunction "DRQ2_B6") (pintype "passive"))
    )
    (net (code "62") (name "unconnected-(X9A-DRQ3-PadB16)") (class "Default")
      (node (ref "X9") (pin "B16") (pinfunction "DRQ3_B16") (pintype "passive"))
    )
    (net (code "63") (name "unconnected-(X9A-ENDXFR-PadB8)") (class "Default")
      (node (ref "X9") (pin "B8") (pinfunction "ENDXFR_B8") (pintype "passive"))
    )
    (net (code "64") (name "unconnected-(X9A-IOCHCHK-PadA1)") (class "Default")
      (node (ref "X9") (pin "A1") (pinfunction "IOCHCHK_A1") (pintype "passive"))
    )
    (net (code "65") (name "unconnected-(X9A-IOCHRDY-PadA10)") (class "Default")
      (node (ref "X9") (pin "A10") (pinfunction "IOCHRDY_A10") (pintype "passive"))
    )
    (net (code "66") (name "unconnected-(X9A-IOR-PadB14)") (class "Default")
      (node (ref "X9") (pin "B14") (pinfunction "IOR_B14") (pintype "passive"))
    )
    (net (code "67") (name "unconnected-(X9A-IOW-PadB13)") (class "Default")
      (node (ref "X9") (pin "B13") (pinfunction "IOW_B13") (pintype "passive"))
    )
    (net (code "68") (name "unconnected-(X9A-IRQ3-PadB25)") (class "Default")
      (node (ref "X9") (pin "B25") (pinfunction "IRQ3_B25") (pintype "passive"))
    )
    (net (code "69") (name "unconnected-(X9A-IRQ4-PadB24)") (class "Default")
      (node (ref "X9") (pin "B24") (pinfunction "IRQ4_B24") (pintype "passive"))
    )
    (net (code "70") (name "unconnected-(X9A-IRQ5-PadB23)") (class "Default")
      (node (ref "X9") (pin "B23") (pinfunction "IRQ5_B23") (pintype "passive"))
    )
    (net (code "71") (name "unconnected-(X9A-IRQ6-PadB22)") (class "Default")
      (node (ref "X9") (pin "B22") (pinfunction "IRQ6_B22") (pintype "passive"))
    )
    (net (code "72") (name "unconnected-(X9A-IRQ7-PadB21)") (class "Default")
      (node (ref "X9") (pin "B21") (pinfunction "IRQ7_B21") (pintype "passive"))
    )
    (net (code "73") (name "unconnected-(X9A-IRQ9-PadB4)") (class "Default")
      (node (ref "X9") (pin "B4") (pinfunction "IRQ9_B4") (pintype "passive"))
    )
    (net (code "74") (name "unconnected-(X9A-KEY-PadB10)") (class "Default")
      (node (ref "X9") (pin "B10") (pinfunction "KEY_B10") (pintype "passive"))
    )
    (net (code "75") (name "unconnected-(X9A-OSC-PadB30)") (class "Default")
      (node (ref "X9") (pin "B30") (pinfunction "OSC_B30") (pintype "passive"))
    )
    (net (code "76") (name "unconnected-(X9A-REFRESH-PadB19)") (class "Default")
      (node (ref "X9") (pin "B19") (pinfunction "REFRESH_B19") (pintype "passive"))
    )
    (net (code "77") (name "unconnected-(X9A-RESETDRV-PadB2)") (class "Default")
      (node (ref "X9") (pin "B2") (pinfunction "RESETDRV_B2") (pintype "passive"))
    )
    (net (code "78") (name "unconnected-(X9A-SA0-PadA31)") (class "Default")
      (node (ref "X9") (pin "A31") (pinfunction "SA0_A31") (pintype "passive"))
    )
    (net (code "79") (name "unconnected-(X9A-SA1-PadA30)") (class "Default")
      (node (ref "X9") (pin "A30") (pinfunction "SA1_A30") (pintype "passive"))
    )
    (net (code "80") (name "unconnected-(X9A-SA2-PadA29)") (class "Default")
      (node (ref "X9") (pin "A29") (pinfunction "SA2_A29") (pintype "passive"))
    )
    (net (code "81") (name "unconnected-(X9A-SA3-PadA28)") (class "Default")
      (node (ref "X9") (pin "A28") (pinfunction "SA3_A28") (pintype "passive"))
    )
    (net (code "82") (name "unconnected-(X9A-SA4-PadA27)") (class "Default")
      (node (ref "X9") (pin "A27") (pinfunction "SA4_A27") (pintype "passive"))
    )
    (net (code "83") (name "unconnected-(X9A-SA5-PadA26)") (class "Default")
      (node (ref "X9") (pin "A26") (pinfunction "SA5_A26") (pintype "passive"))
    )
    (net (code "84") (name "unconnected-(X9A-SA6-PadA25)") (class "Default")
      (node (ref "X9") (pin "A25") (pinfunction "SA6_A25") (pintype "passive"))
    )
    (net (code "85") (name "unconnected-(X9A-SA7-PadA24)") (class "Default")
      (node (ref "X9") (pin "A24") (pinfunction "SA7_A24") (pintype "passive"))
    )
    (net (code "86") (name "unconnected-(X9A-SA8-PadA23)") (class "Default")
      (node (ref "X9") (pin "A23") (pinfunction "SA8_A23") (pintype "passive"))
    )
    (net (code "87") (name "unconnected-(X9A-SA9-PadA22)") (class "Default")
      (node (ref "X9") (pin "A22") (pinfunction "SA9_A22") (pintype "passive"))
    )
    (net (code "88") (name "unconnected-(X9A-SA10-PadA21)") (class "Default")
      (node (ref "X9") (pin "A21") (pinfunction "SA10_A21") (pintype "passive"))
    )
    (net (code "89") (name "unconnected-(X9A-SA11-PadA20)") (class "Default")
      (node (ref "X9") (pin "A20") (pinfunction "SA11_A20") (pintype "passive"))
    )
    (net (code "90") (name "unconnected-(X9A-SA12-PadA19)") (class "Default")
      (node (ref "X9") (pin "A19") (pinfunction "SA12_A19") (pintype "passive"))
    )
    (net (code "91") (name "unconnected-(X9A-SA13-PadA18)") (class "Default")
      (node (ref "X9") (pin "A18") (pinfunction "SA13_A18") (pintype "passive"))
    )
    (net (code "92") (name "unconnected-(X9A-SA14-PadA17)") (class "Default")
      (node (ref "X9") (pin "A17") (pinfunction "SA14_A17") (pintype "passive"))
    )
    (net (code "93") (name "unconnected-(X9A-SA15-PadA16)") (class "Default")
      (node (ref "X9") (pin "A16") (pinfunction "SA15_A16") (pintype "passive"))
    )
    (net (code "94") (name "unconnected-(X9A-SA16-PadA15)") (class "Default")
      (node (ref "X9") (pin "A15") (pinfunction "SA16_A15") (pintype "passive"))
    )
    (net (code "95") (name "unconnected-(X9A-SA17-PadA14)") (class "Default")
      (node (ref "X9") (pin "A14") (pinfunction "SA17_A14") (pintype "passive"))
    )
    (net (code "96") (name "unconnected-(X9A-SA18-PadA13)") (class "Default")
      (node (ref "X9") (pin "A13") (pinfunction "SA18_A13") (pintype "passive"))
    )
    (net (code "97") (name "unconnected-(X9A-SA19-PadA12)") (class "Default")
      (node (ref "X9") (pin "A12") (pinfunction "SA19_A12") (pintype "passive"))
    )
    (net (code "98") (name "unconnected-(X9A-SD0-PadA9)") (class "Default")
      (node (ref "X9") (pin "A9") (pinfunction "SD0_A9") (pintype "passive"))
    )
    (net (code "99") (name "unconnected-(X9A-SD1-PadA8)") (class "Default")
      (node (ref "X9") (pin "A8") (pinfunction "SD1_A8") (pintype "passive"))
    )
    (net (code "100") (name "unconnected-(X9A-SD2-PadA7)") (class "Default")
      (node (ref "X9") (pin "A7") (pinfunction "SD2_A7") (pintype "passive"))
    )
    (net (code "101") (name "unconnected-(X9A-SD3-PadA6)") (class "Default")
      (node (ref "X9") (pin "A6") (pinfunction "SD3_A6") (pintype "passive"))
    )
    (net (code "102") (name "unconnected-(X9A-SD4-PadA5)") (class "Default")
      (node (ref "X9") (pin "A5") (pinfunction "SD4_A5") (pintype "passive"))
    )
    (net (code "103") (name "unconnected-(X9A-SD5-PadA4)") (class "Default")
      (node (ref "X9") (pin "A4") (pinfunction "SD5_A4") (pintype "passive"))
    )
    (net (code "104") (name "unconnected-(X9A-SD6-PadA3)") (class "Default")
      (node (ref "X9") (pin "A3") (pinfunction "SD6_A3") (pintype "passive"))
    )
    (net (code "105") (name "unconnected-(X9A-SD7-PadA2)") (class "Default")
      (node (ref "X9") (pin "A2") (pinfunction "SD7_A2") (pintype "passive"))
    )
    (net (code "106") (name "unconnected-(X9A-SMEMR-PadB12)") (class "Default")
      (node (ref "X9") (pin "B12") (pinfunction "SMEMR_B12") (pintype "passive"))
    )
    (net (code "107") (name "unconnected-(X9A-SMEMW-PadB11)") (class "Default")
      (node (ref "X9") (pin "B11") (pinfunction "SMEMW_B11") (pintype "passive"))
    )
    (net (code "108") (name "unconnected-(X9A-SYSCLK-PadB20)") (class "Default")
      (node (ref "X9") (pin "B20") (pinfunction "SYSCLK_B20") (pintype "passive"))
    )
    (net (code "109") (name "unconnected-(X9A-TC-PadB27)") (class "Default")
      (node (ref "X9") (pin "B27") (pinfunction "TC_B27") (pintype "passive"))
    )
    (net (code "110") (name "unconnected-(X9B-+5V-PadD16)") (class "Default")
      (node (ref "X9") (pin "D16") (pinfunction "+5V_D16") (pintype "passive"))
    )
    (net (code "111") (name "unconnected-(X9B-DACK0-PadD8)") (class "Default")
      (node (ref "X9") (pin "D8") (pinfunction "DACK0_D8") (pintype "passive"))
    )
    (net (code "112") (name "unconnected-(X9B-DACK5-PadD10)") (class "Default")
      (node (ref "X9") (pin "D10") (pinfunction "DACK5_D10") (pintype "passive"))
    )
    (net (code "113") (name "unconnected-(X9B-DACK6-PadD12)") (class "Default")
      (node (ref "X9") (pin "D12") (pinfunction "DACK6_D12") (pintype "passive"))
    )
    (net (code "114") (name "unconnected-(X9B-DACK7-PadD14)") (class "Default")
      (node (ref "X9") (pin "D14") (pinfunction "DACK7_D14") (pintype "passive"))
    )
    (net (code "115") (name "unconnected-(X9B-DRQ0-PadD9)") (class "Default")
      (node (ref "X9") (pin "D9") (pinfunction "DRQ0_D9") (pintype "passive"))
    )
    (net (code "116") (name "unconnected-(X9B-DRQ5-PadD11)") (class "Default")
      (node (ref "X9") (pin "D11") (pinfunction "DRQ5_D11") (pintype "passive"))
    )
    (net (code "117") (name "unconnected-(X9B-DRQ6-PadD13)") (class "Default")
      (node (ref "X9") (pin "D13") (pinfunction "DRQ6_D13") (pintype "passive"))
    )
    (net (code "118") (name "unconnected-(X9B-DRQ7-PadD15)") (class "Default")
      (node (ref "X9") (pin "D15") (pinfunction "DRQ7_D15") (pintype "passive"))
    )
    (net (code "119") (name "unconnected-(X9B-IOCS16-PadD2)") (class "Default")
      (node (ref "X9") (pin "D2") (pinfunction "IOCS16_D2") (pintype "passive"))
    )
    (net (code "120") (name "unconnected-(X9B-IRQ10-PadD3)") (class "Default")
      (node (ref "X9") (pin "D3") (pinfunction "IRQ10_D3") (pintype "passive"))
    )
    (net (code "121") (name "unconnected-(X9B-IRQ11-PadD4)") (class "Default")
      (node (ref "X9") (pin "D4") (pinfunction "IRQ11_D4") (pintype "passive"))
    )
    (net (code "122") (name "unconnected-(X9B-IRQ12-PadD5)") (class "Default")
      (node (ref "X9") (pin "D5") (pinfunction "IRQ12_D5") (pintype "passive"))
    )
    (net (code "123") (name "unconnected-(X9B-IRQ14-PadD7)") (class "Default")
      (node (ref "X9") (pin "D7") (pinfunction "IRQ14_D7") (pintype "passive"))
    )
    (net (code "124") (name "unconnected-(X9B-IRQ15-PadD6)") (class "Default")
      (node (ref "X9") (pin "D6") (pinfunction "IRQ15_D6") (pintype "passive"))
    )
    (net (code "125") (name "unconnected-(X9B-KEY-PadC19)") (class "Default")
      (node (ref "X9") (pin "C19") (pinfunction "KEY_C19") (pintype "passive"))
    )
    (net (code "126") (name "unconnected-(X9B-LA17-PadC8)") (class "Default")
      (node (ref "X9") (pin "C8") (pinfunction "LA17_C8") (pintype "passive"))
    )
    (net (code "127") (name "unconnected-(X9B-LA18-PadC7)") (class "Default")
      (node (ref "X9") (pin "C7") (pinfunction "LA18_C7") (pintype "passive"))
    )
    (net (code "128") (name "unconnected-(X9B-LA19-PadC6)") (class "Default")
      (node (ref "X9") (pin "C6") (pinfunction "LA19_C6") (pintype "passive"))
    )
    (net (code "129") (name "unconnected-(X9B-LA20-PadC5)") (class "Default")
      (node (ref "X9") (pin "C5") (pinfunction "LA20_C5") (pintype "passive"))
    )
    (net (code "130") (name "unconnected-(X9B-LA21-PadC4)") (class "Default")
      (node (ref "X9") (pin "C4") (pinfunction "LA21_C4") (pintype "passive"))
    )
    (net (code "131") (name "unconnected-(X9B-LA22-PadC3)") (class "Default")
      (node (ref "X9") (pin "C3") (pinfunction "LA22_C3") (pintype "passive"))
    )
    (net (code "132") (name "unconnected-(X9B-LA23-PadC2)") (class "Default")
      (node (ref "X9") (pin "C2") (pinfunction "LA23_C2") (pintype "passive"))
    )
    (net (code "133") (name "unconnected-(X9B-MASTER-PadD17)") (class "Default")
      (node (ref "X9") (pin "D17") (pinfunction "MASTER_D17") (pintype "passive"))
    )
    (net (code "134") (name "unconnected-(X9B-MEMCS16-PadD1)") (class "Default")
      (node (ref "X9") (pin "D1") (pinfunction "MEMCS16_D1") (pintype "passive"))
    )
    (net (code "135") (name "unconnected-(X9B-MEMR-PadC9)") (class "Default")
      (node (ref "X9") (pin "C9") (pinfunction "MEMR_C9") (pintype "passive"))
    )
    (net (code "136") (name "unconnected-(X9B-MEMW-PadC10)") (class "Default")
      (node (ref "X9") (pin "C10") (pinfunction "MEMW_C10") (pintype "passive"))
    )
    (net (code "137") (name "unconnected-(X9B-SBHE-PadC1)") (class "Default")
      (node (ref "X9") (pin "C1") (pinfunction "SBHE_C1") (pintype "passive"))
    )
    (net (code "138") (name "unconnected-(X9B-SD8-PadC11)") (class "Default")
      (node (ref "X9") (pin "C11") (pinfunction "SD8_C11") (pintype "passive"))
    )
    (net (code "139") (name "unconnected-(X9B-SD9-PadC12)") (class "Default")
      (node (ref "X9") (pin "C12") (pinfunction "SD9_C12") (pintype "passive"))
    )
    (net (code "140") (name "unconnected-(X9B-SD10-PadC13)") (class "Default")
      (node (ref "X9") (pin "C13") (pinfunction "SD10_C13") (pintype "passive"))
    )
    (net (code "141") (name "unconnected-(X9B-SD11-PadC14)") (class "Default")
      (node (ref "X9") (pin "C14") (pinfunction "SD11_C14") (pintype "passive"))
    )
    (net (code "142") (name "unconnected-(X9B-SD12-PadC15)") (class "Default")
      (node (ref "X9") (pin "C15") (pinfunction "SD12_C15") (pintype "passive"))
    )
    (net (code "143") (name "unconnected-(X9B-SD13-PadC16)") (class "Default")
      (node (ref "X9") (pin "C16") (pinfunction "SD13_C16") (pintype "passive"))
    )
    (net (code "144") (name "unconnected-(X9B-SD14-PadC17)") (class "Default")
      (node (ref "X9") (pin "C17") (pinfunction "SD14_C17") (pintype "passive"))
    )
    (net (code "145") (name "unconnected-(X9B-SD15-PadC18)") (class "Default")
      (node (ref "X9") (pin "C18") (pinfunction "SD15_C18") (pintype "passive"))
    )
  )
)
